# streams_v05.net
KiCad netlist of a schematic drawn in EAGLE
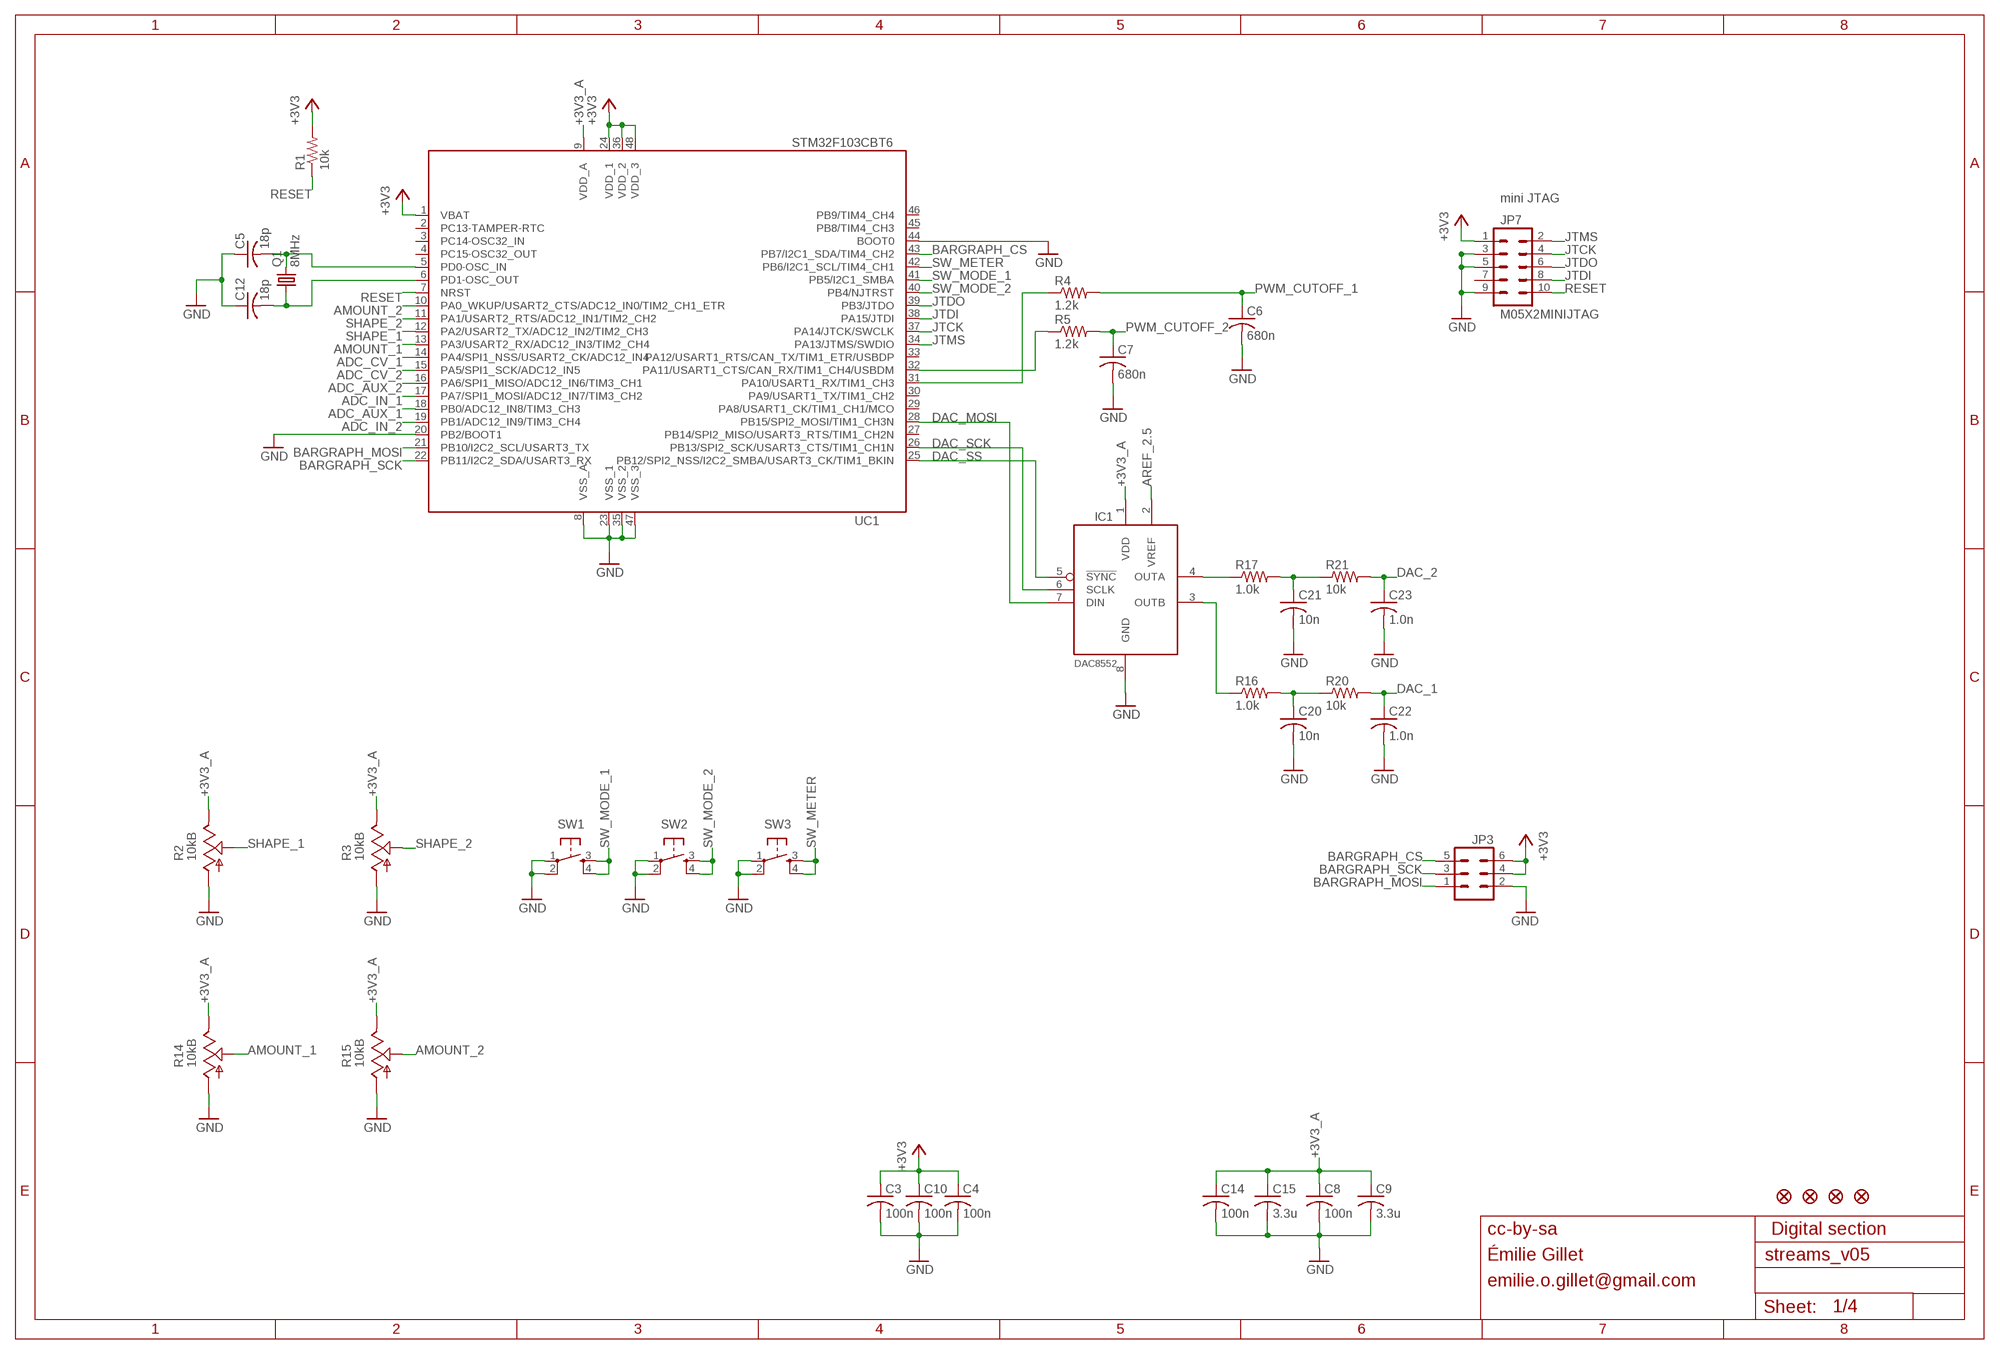
[diagram p0: schematic, sheet 1]
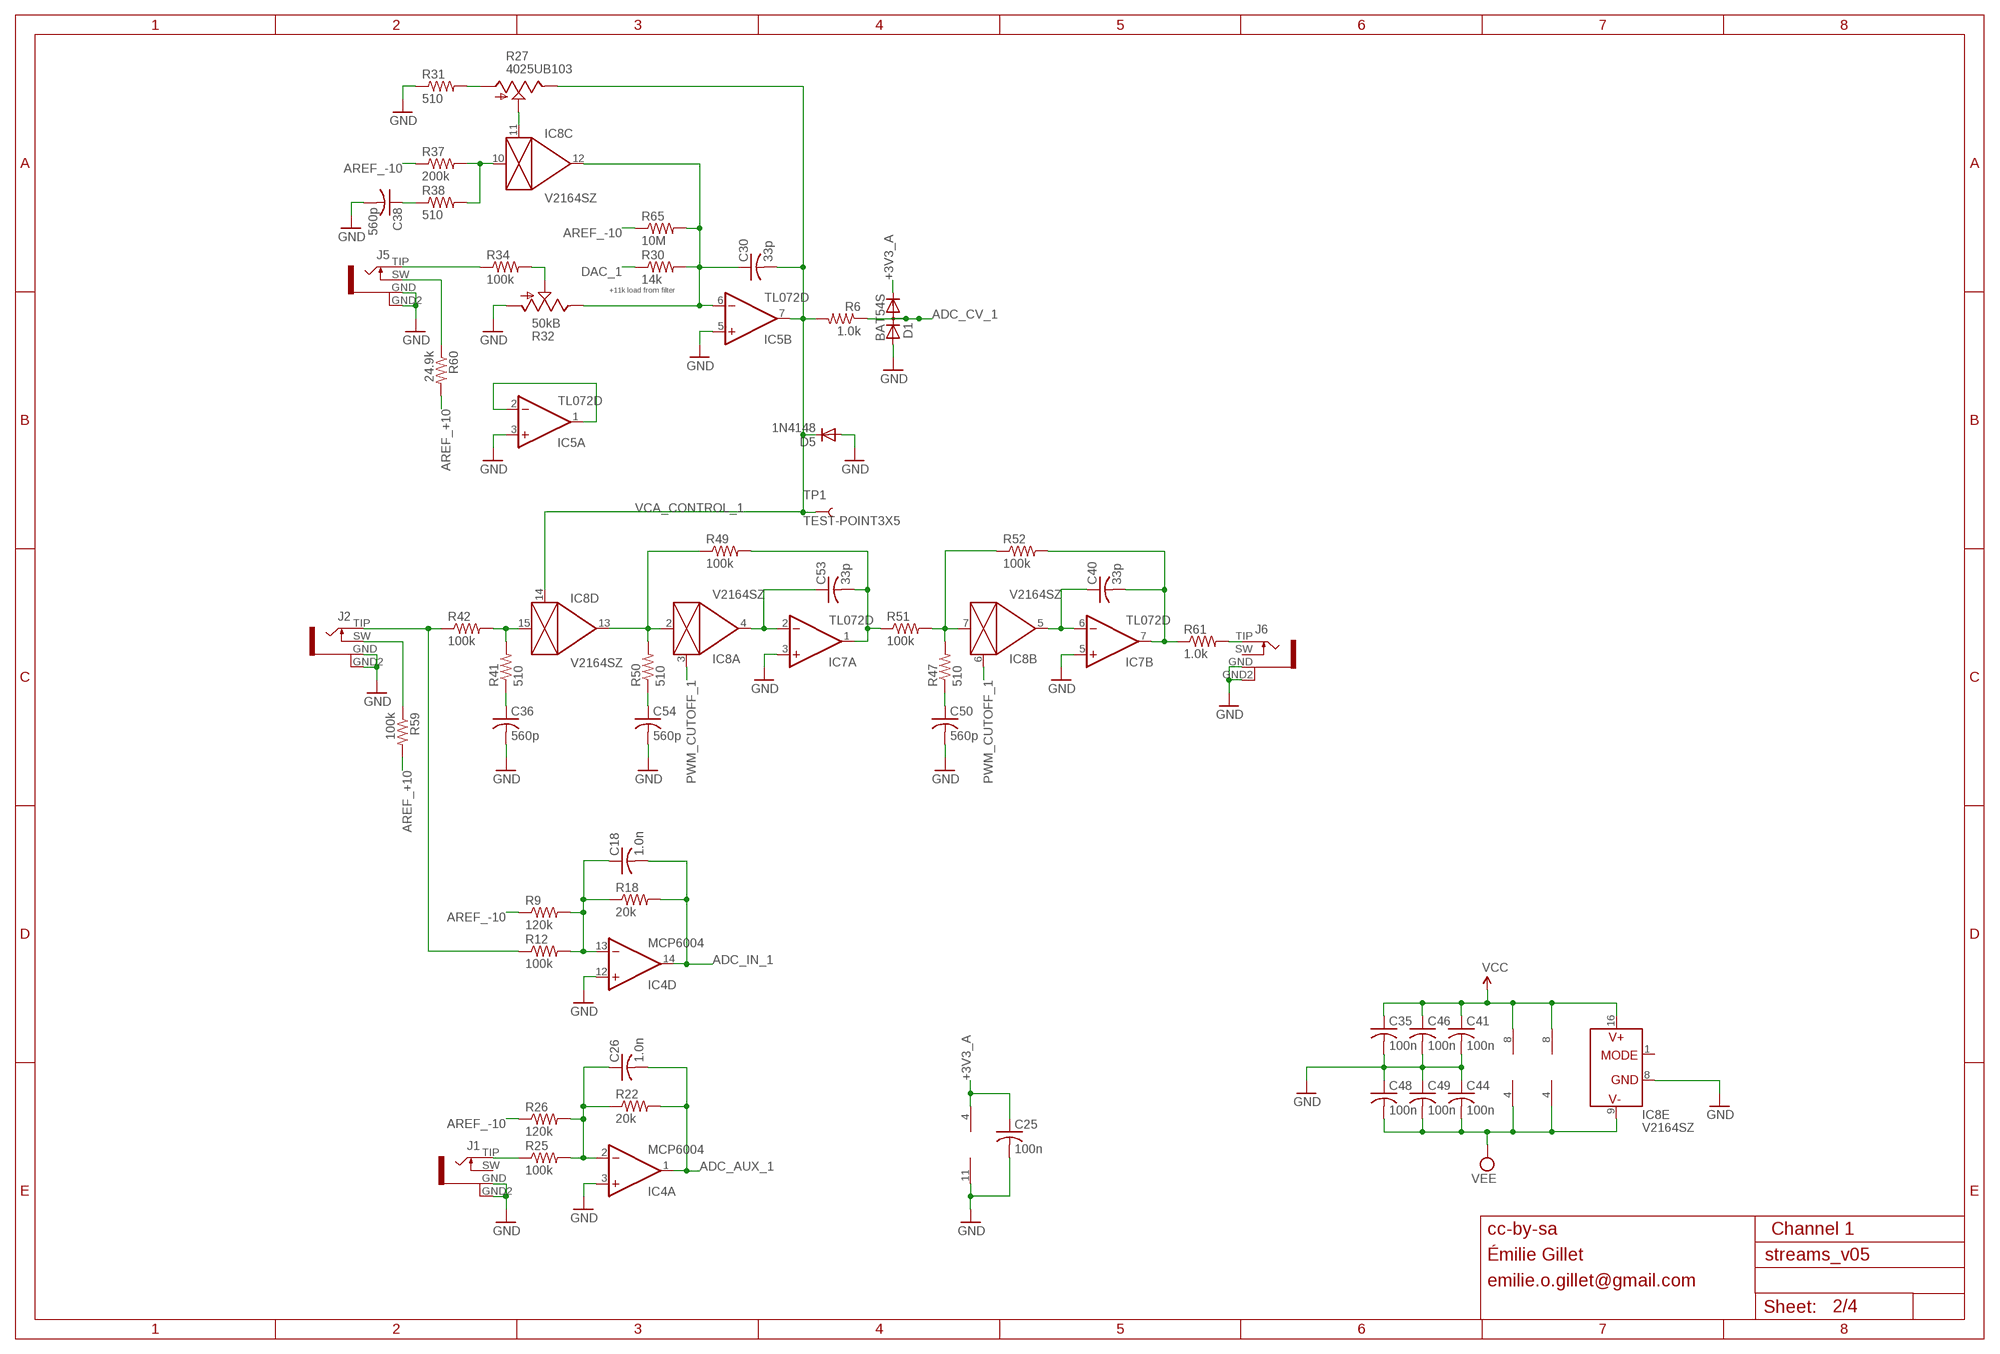
[diagram p1: schematic, sheet 2]
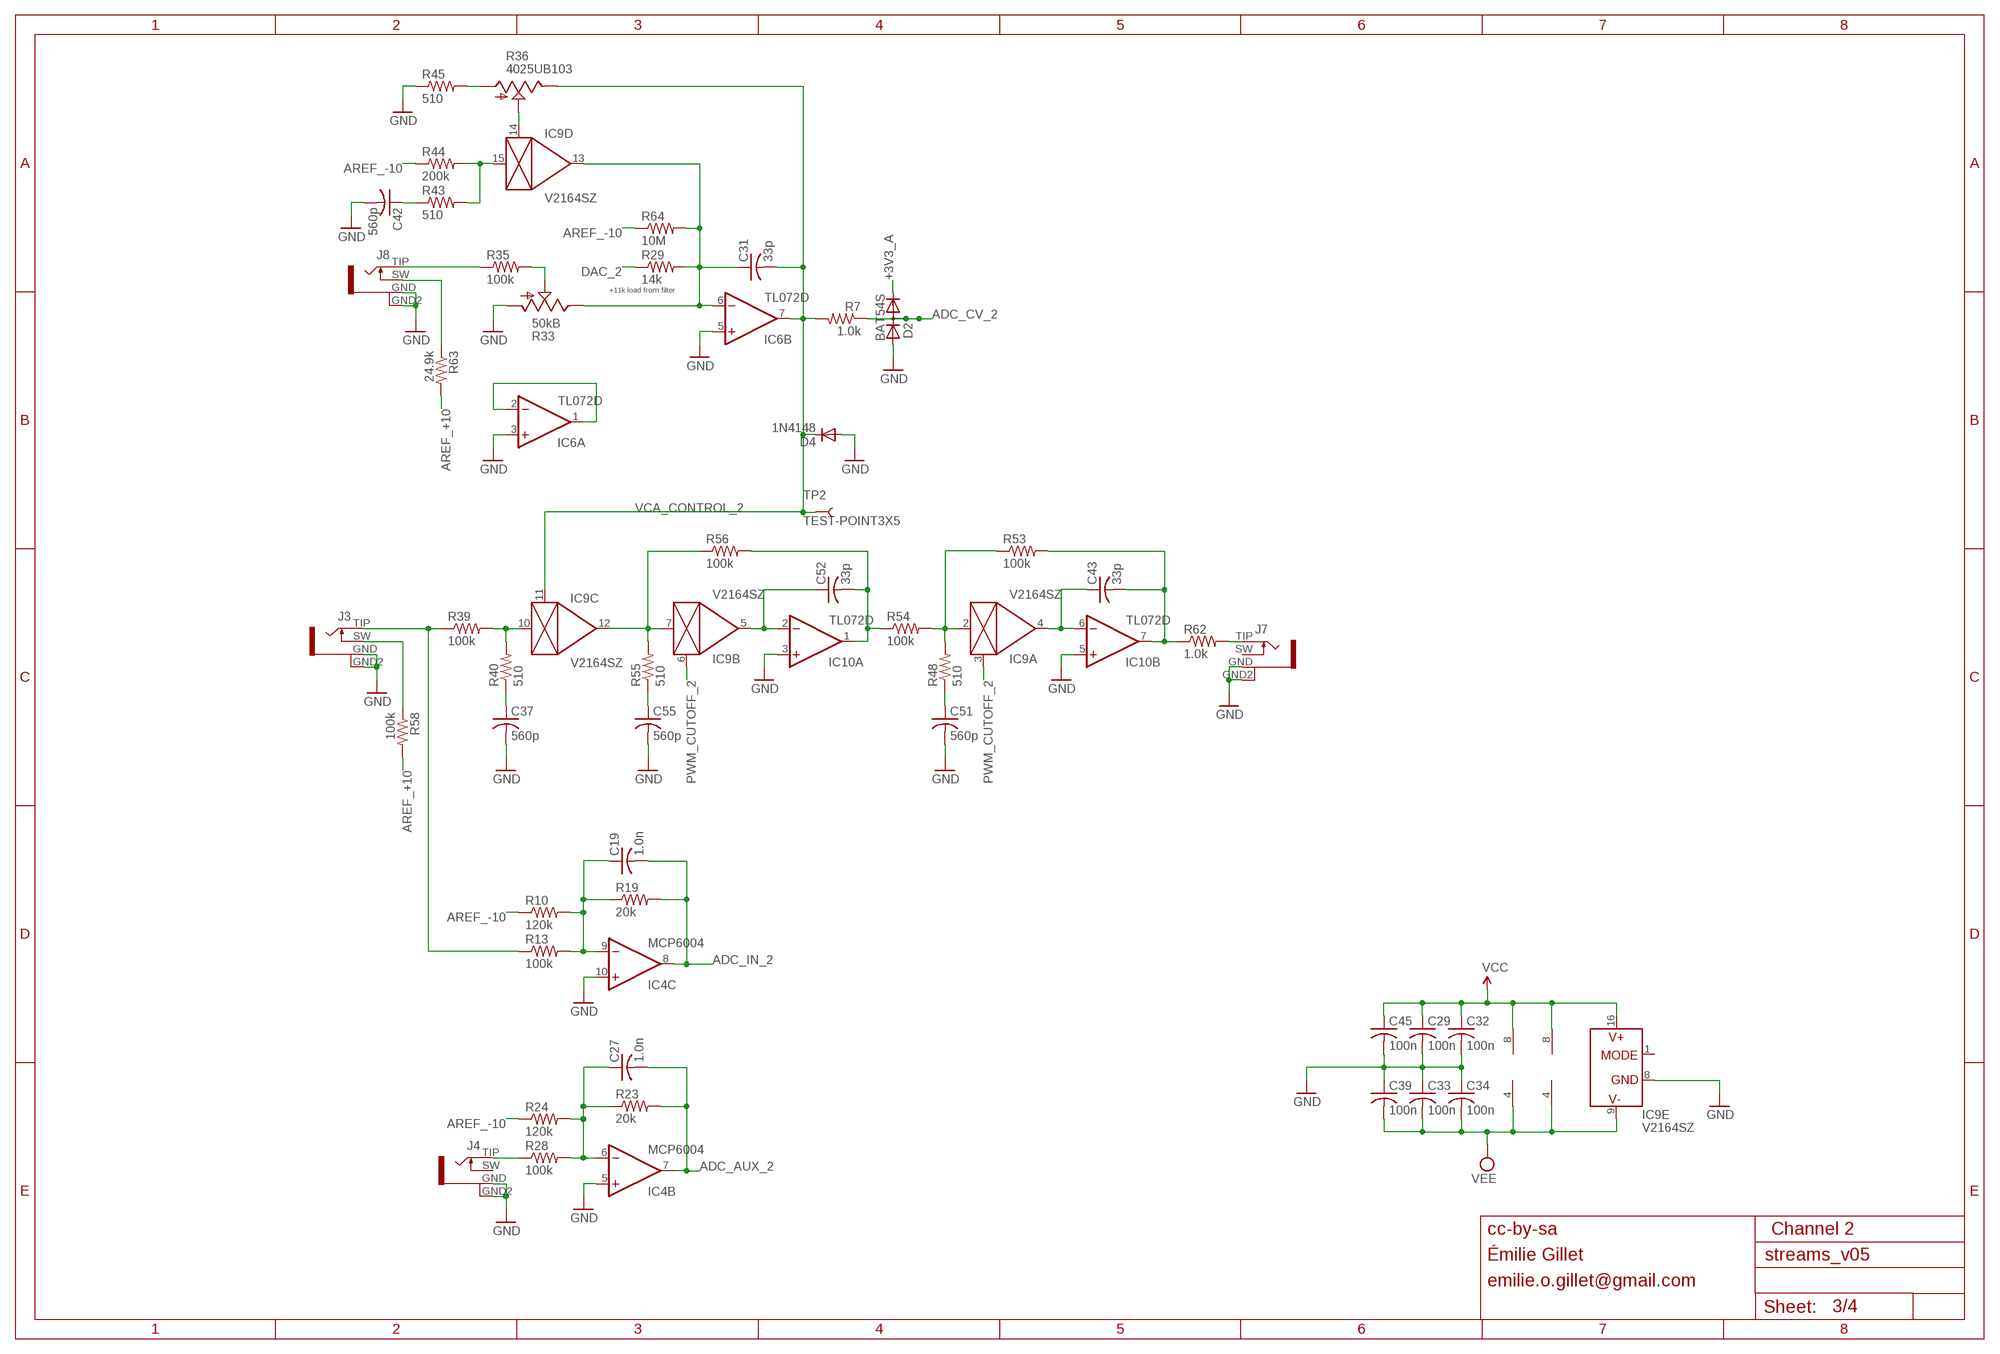
[diagram p2: schematic, sheet 3]
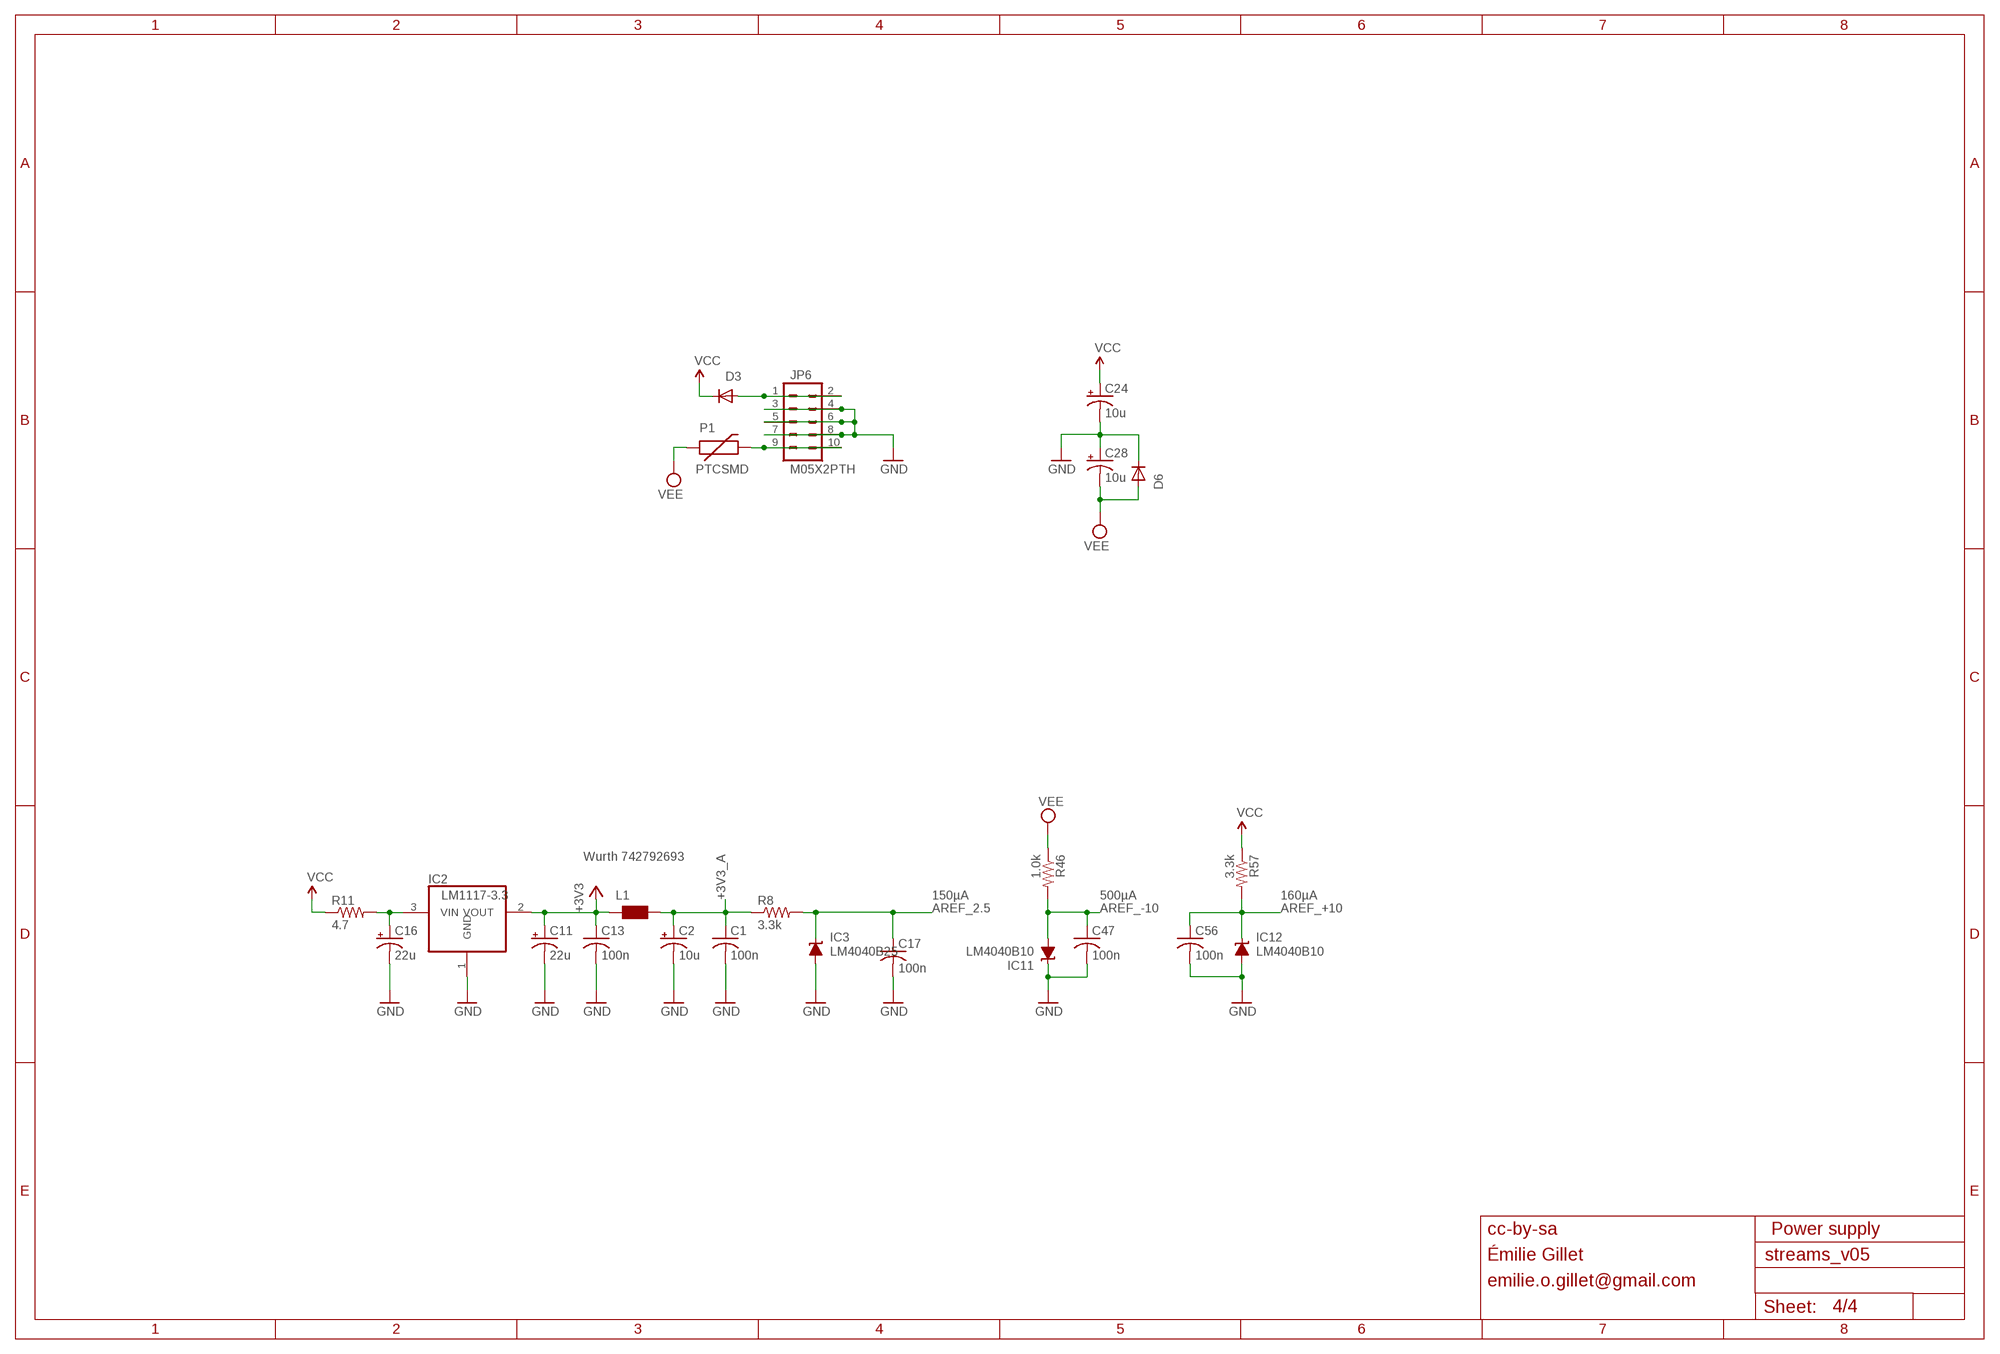
[diagram p3: schematic, sheet 4]

(export (version "E")
  (design (tool "Eeschema 10.0.6"))
  (components
    (comp (ref "C19")
      (value "1.0n")
      (footprint "eagle-import:C0603")
      (libsource (lib "eagle-import") (part "C-USC0603"))
    )
    (comp (ref "C27")
      (value "1.0n")
      (footprint "eagle-import:C0603")
      (libsource (lib "eagle-import") (part "C-USC0603"))
    )
    (comp (ref "C29")
      (value "100n")
      (footprint "eagle-import:C0603")
      (libsource (lib "eagle-import") (part "C-USC0603"))
    )
    (comp (ref "C31")
      (value "33p")
      (footprint "eagle-import:C0603")
      (libsource (lib "eagle-import") (part "C-USC0603"))
    )
    (comp (ref "C32")
      (value "100n")
      (footprint "eagle-import:C0603")
      (libsource (lib "eagle-import") (part "C-USC0603"))
    )
    (comp (ref "C33")
      (value "100n")
      (footprint "eagle-import:C0603")
      (libsource (lib "eagle-import") (part "C-USC0603"))
    )
    (comp (ref "C34")
      (value "100n")
      (footprint "eagle-import:C0603")
      (libsource (lib "eagle-import") (part "C-USC0603"))
    )
    (comp (ref "C37")
      (value "560p")
      (footprint "eagle-import:C0603")
      (libsource (lib "eagle-import") (part "C-USC0603"))
    )
    (comp (ref "C39")
      (value "100n")
      (footprint "eagle-import:C0603")
      (libsource (lib "eagle-import") (part "C-USC0603"))
    )
    (comp (ref "C42")
      (value "560p")
      (footprint "eagle-import:C0603")
      (libsource (lib "eagle-import") (part "C-USC0603"))
    )
    (comp (ref "C43")
      (value "33p")
      (footprint "eagle-import:C0603")
      (libsource (lib "eagle-import") (part "C-USC0603"))
    )
    (comp (ref "C45")
      (value "100n")
      (footprint "eagle-import:C0603")
      (libsource (lib "eagle-import") (part "C-USC0603"))
    )
    (comp (ref "C51")
      (value "560p")
      (footprint "eagle-import:C0603")
      (libsource (lib "eagle-import") (part "C-USC0603"))
    )
    (comp (ref "C52")
      (value "33p")
      (footprint "eagle-import:C0603")
      (libsource (lib "eagle-import") (part "C-USC0603"))
    )
    (comp (ref "C55")
      (value "560p")
      (footprint "eagle-import:C0603")
      (libsource (lib "eagle-import") (part "C-USC0603"))
    )
    (comp (ref "D2")
      (value "BAT54S")
      (footprint "eagle-import:SOT23")
      (libsource (lib "eagle-import") (part "DIODE_2CACA-SOT23"))
    )
    (comp (ref "D4")
      (value "1N4148")
      (footprint "eagle-import:SOD323-W")
      (libsource (lib "eagle-import") (part "DIODE-SOD323-W"))
    )
    (comp (ref "IC4")
      (value "MCP6004")
      (footprint "eagle-import:SO14")
      (libsource (lib "eagle-import") (part "TL074D"))
    )
    (comp (ref "IC6")
      (value "TL072D")
      (footprint "eagle-import:SO08")
      (libsource (lib "eagle-import") (part "TL072D"))
    )
    (comp (ref "IC9")
      (value "V2164SZ")
      (footprint "eagle-import:SOIC16N")
      (libsource (lib "eagle-import") (part "SSM2164S"))
    )
    (comp (ref "IC10")
      (value "TL072D")
      (footprint "eagle-import:SO08")
      (libsource (lib "eagle-import") (part "TL072D"))
    )
    (comp (ref "J3")
      (value "PJ301WQP")
      (footprint "eagle-import:WQP_PJ_301BM_WIDER")
      (libsource (lib "eagle-import") (part "PJ301WQP"))
    )
    (comp (ref "J4")
      (value "PJ301WQP")
      (footprint "eagle-import:WQP_PJ_301BM_WIDER")
      (libsource (lib "eagle-import") (part "PJ301WQP"))
    )
    (comp (ref "J7")
      (value "PJ301WQP")
      (footprint "eagle-import:WQP_PJ_301BM_WIDER")
      (libsource (lib "eagle-import") (part "PJ301WQP"))
    )
    (comp (ref "J8")
      (value "PJ301WQP")
      (footprint "eagle-import:WQP_PJ_301BM_WIDER")
      (libsource (lib "eagle-import") (part "PJ301WQP"))
    )
    (comp (ref "R7")
      (value "1.0k")
      (footprint "eagle-import:R0603")
      (libsource (lib "eagle-import") (part "R-US_R0603"))
    )
    (comp (ref "R10")
      (value "120k")
      (footprint "eagle-import:R0603")
      (libsource (lib "eagle-import") (part "R-US_R0603"))
    )
    (comp (ref "R13")
      (value "100k")
      (footprint "eagle-import:R0603")
      (libsource (lib "eagle-import") (part "R-US_R0603"))
    )
    (comp (ref "R19")
      (value "20k")
      (footprint "eagle-import:R0603")
      (libsource (lib "eagle-import") (part "R-US_R0603"))
    )
    (comp (ref "R23")
      (value "20k")
      (footprint "eagle-import:R0603")
      (libsource (lib "eagle-import") (part "R-US_R0603"))
    )
    (comp (ref "R24")
      (value "120k")
      (footprint "eagle-import:R0603")
      (libsource (lib "eagle-import") (part "R-US_R0603"))
    )
    (comp (ref "R28")
      (value "100k")
      (footprint "eagle-import:R0603")
      (libsource (lib "eagle-import") (part "R-US_R0603"))
    )
    (comp (ref "R29")
      (value "14k")
      (footprint "eagle-import:R0603")
      (libsource (lib "eagle-import") (part "R-US_R0603"))
    )
    (comp (ref "R33")
      (value "50kB")
      (footprint "eagle-import:ALPS_POT_VERTICAL_PS")
      (libsource (lib "eagle-import") (part "POT_USVERTICAL_PS"))
    )
    (comp (ref "R35")
      (value "100k")
      (footprint "eagle-import:R0603")
      (libsource (lib "eagle-import") (part "R-US_R0603"))
    )
    (comp (ref "R36")
      (value "4025UB103")
      (footprint "eagle-import:ALPS_POT_VERTICAL")
      (libsource (lib "eagle-import") (part "POT_USVERTICAL"))
    )
    (comp (ref "R39")
      (value "100k")
      (footprint "eagle-import:R0603")
      (libsource (lib "eagle-import") (part "R-US_R0603"))
    )
    (comp (ref "R40")
      (value "510")
      (footprint "eagle-import:R0603")
      (libsource (lib "eagle-import") (part "R-US_R0603"))
    )
    (comp (ref "R43")
      (value "510")
      (footprint "eagle-import:R0603")
      (libsource (lib "eagle-import") (part "R-US_R0603"))
    )
    (comp (ref "R44")
      (value "200k")
      (footprint "eagle-import:R0603")
      (libsource (lib "eagle-import") (part "R-US_R0603"))
    )
    (comp (ref "R45")
      (value "510")
      (footprint "eagle-import:R0603")
      (libsource (lib "eagle-import") (part "R-US_R0603"))
    )
    (comp (ref "R48")
      (value "510")
      (footprint "eagle-import:R0603")
      (libsource (lib "eagle-import") (part "R-US_R0603"))
    )
    (comp (ref "R53")
      (value "100k")
      (footprint "eagle-import:R0603")
      (libsource (lib "eagle-import") (part "R-US_R0603"))
    )
    (comp (ref "R54")
      (value "100k")
      (footprint "eagle-import:R0603")
      (libsource (lib "eagle-import") (part "R-US_R0603"))
    )
    (comp (ref "R55")
      (value "510")
      (footprint "eagle-import:R0603")
      (libsource (lib "eagle-import") (part "R-US_R0603"))
    )
    (comp (ref "R56")
      (value "100k")
      (footprint "eagle-import:R0603")
      (libsource (lib "eagle-import") (part "R-US_R0603"))
    )
    (comp (ref "R58")
      (value "100k")
      (footprint "eagle-import:R0603")
      (libsource (lib "eagle-import") (part "R-US_R0603"))
    )
    (comp (ref "R62")
      (value "1.0k")
      (footprint "eagle-import:R0603")
      (libsource (lib "eagle-import") (part "R-US_R0603"))
    )
    (comp (ref "R63")
      (value "24.9k")
      (footprint "eagle-import:R0603")
      (libsource (lib "eagle-import") (part "R-US_R0603"))
    )
    (comp (ref "R64")
      (value "10M")
      (footprint "eagle-import:R0603")
      (libsource (lib "eagle-import") (part "R-US_R0603"))
    )
    (comp (ref "TP2")
      (value "TEST-POINT3X5")
      (footprint "eagle-import:PAD.03X.05")
      (libsource (lib "eagle-import") (part "TEST-POINT3X5"))
    )
    (comp (ref "C3")
      (value "100n")
      (footprint "eagle-import:C0603")
      (libsource (lib "eagle-import") (part "C-USC0603"))
    )
    (comp (ref "C4")
      (value "100n")
      (footprint "eagle-import:C0603")
      (libsource (lib "eagle-import") (part "C-USC0603"))
    )
    (comp (ref "C5")
      (value "18p")
      (footprint "eagle-import:C0603")
      (libsource (lib "eagle-import") (part "C-USC0603"))
    )
    (comp (ref "C6")
      (value "680n")
      (footprint "eagle-import:C0603")
      (libsource (lib "eagle-import") (part "C-USC0603"))
    )
    (comp (ref "C7")
      (value "680n")
      (footprint "eagle-import:C0603")
      (libsource (lib "eagle-import") (part "C-USC0603"))
    )
    (comp (ref "C8")
      (value "100n")
      (footprint "eagle-import:C0603")
      (libsource (lib "eagle-import") (part "C-USC0603"))
    )
    (comp (ref "C9")
      (value "3.3u")
      (footprint "eagle-import:C0603")
      (libsource (lib "eagle-import") (part "C-USC0603"))
    )
    (comp (ref "C10")
      (value "100n")
      (footprint "eagle-import:C0603")
      (libsource (lib "eagle-import") (part "C-USC0603"))
    )
    (comp (ref "C12")
      (value "18p")
      (footprint "eagle-import:C0603")
      (libsource (lib "eagle-import") (part "C-USC0603"))
    )
    (comp (ref "C14")
      (value "100n")
      (footprint "eagle-import:C0603")
      (libsource (lib "eagle-import") (part "C-USC0603"))
    )
    (comp (ref "C15")
      (value "3.3u")
      (footprint "eagle-import:C0603")
      (libsource (lib "eagle-import") (part "C-USC0603"))
    )
    (comp (ref "C20")
      (value "10n")
      (footprint "eagle-import:C0603")
      (libsource (lib "eagle-import") (part "C-USC0603"))
    )
    (comp (ref "C21")
      (value "10n")
      (footprint "eagle-import:C0603")
      (libsource (lib "eagle-import") (part "C-USC0603"))
    )
    (comp (ref "C22")
      (value "1.0n")
      (footprint "eagle-import:C0603")
      (libsource (lib "eagle-import") (part "C-USC0603"))
    )
    (comp (ref "C23")
      (value "1.0n")
      (footprint "eagle-import:C0603")
      (libsource (lib "eagle-import") (part "C-USC0603"))
    )
    (comp (ref "IC1")
      (value "DAC8552")
      (footprint "eagle-import:MSOP-8")
      (libsource (lib "eagle-import") (part "DAC8552"))
    )
    (comp (ref "JP1")
      (value "FIDUCIAL1X2")
      (footprint "eagle-import:FIDUCIAL-1X2")
      (libsource (lib "eagle-import") (part "FIDUCIAL1X2"))
    )
    (comp (ref "JP2")
      (value "FIDUCIAL1X2")
      (footprint "eagle-import:FIDUCIAL-1X2")
      (libsource (lib "eagle-import") (part "FIDUCIAL1X2"))
    )
    (comp (ref "JP3")
      (value "M03X2BOTTOM")
      (footprint "eagle-import:2X3_BOTTOM")
      (libsource (lib "eagle-import") (part "M03X2BOTTOM"))
    )
    (comp (ref "JP4")
      (value "FIDUCIAL1X2")
      (footprint "eagle-import:FIDUCIAL-1X2")
      (libsource (lib "eagle-import") (part "FIDUCIAL1X2"))
    )
    (comp (ref "JP5")
      (value "FIDUCIAL1X2")
      (footprint "eagle-import:FIDUCIAL-1X2")
      (libsource (lib "eagle-import") (part "FIDUCIAL1X2"))
    )
    (comp (ref "JP7")
      (value "M05X2MINIJTAG")
      (footprint "eagle-import:2X5-1.27")
      (libsource (lib "eagle-import") (part "M05X2MINIJTAG"))
    )
    (comp (ref "Q1")
      (value "8MHz")
      (footprint "eagle-import:HC49UP")
      (libsource (lib "eagle-import") (part "CRYSTALHC49UP"))
    )
    (comp (ref "R1")
      (value "10k")
      (footprint "eagle-import:R0603")
      (libsource (lib "eagle-import") (part "R-US_R0603"))
    )
    (comp (ref "R2")
      (value "10kB")
      (footprint "eagle-import:ALPS_POT_VERTICAL_PS")
      (libsource (lib "eagle-import") (part "POT_USVERTICAL_PS"))
    )
    (comp (ref "R3")
      (value "10kB")
      (footprint "eagle-import:ALPS_POT_VERTICAL_PS")
      (libsource (lib "eagle-import") (part "POT_USVERTICAL_PS"))
    )
    (comp (ref "R4")
      (value "1.2k")
      (footprint "eagle-import:R0603")
      (libsource (lib "eagle-import") (part "R-US_R0603"))
    )
    (comp (ref "R5")
      (value "1.2k")
      (footprint "eagle-import:R0603")
      (libsource (lib "eagle-import") (part "R-US_R0603"))
    )
    (comp (ref "R14")
      (value "10kB")
      (footprint "eagle-import:ALPS_POT_VERTICAL_PS")
      (libsource (lib "eagle-import") (part "POT_USVERTICAL_PS"))
    )
    (comp (ref "R15")
      (value "10kB")
      (footprint "eagle-import:ALPS_POT_VERTICAL_PS")
      (libsource (lib "eagle-import") (part "POT_USVERTICAL_PS"))
    )
    (comp (ref "R16")
      (value "1.0k")
      (footprint "eagle-import:R0603")
      (libsource (lib "eagle-import") (part "R-US_R0603"))
    )
    (comp (ref "R17")
      (value "1.0k")
      (footprint "eagle-import:R0603")
      (libsource (lib "eagle-import") (part "R-US_R0603"))
    )
    (comp (ref "R20")
      (value "10k")
      (footprint "eagle-import:R0603")
      (libsource (lib "eagle-import") (part "R-US_R0603"))
    )
    (comp (ref "R21")
      (value "10k")
      (footprint "eagle-import:R0603")
      (libsource (lib "eagle-import") (part "R-US_R0603"))
    )
    (comp (ref "SW1")
      (value "TAC_SWITCHPTH")
      (footprint "eagle-import:TACTILE-PTH")
      (libsource (lib "eagle-import") (part "TAC_SWITCHPTH"))
    )
    (comp (ref "SW2")
      (value "TAC_SWITCHPTH")
      (footprint "eagle-import:TACTILE-PTH")
      (libsource (lib "eagle-import") (part "TAC_SWITCHPTH"))
    )
    (comp (ref "SW3")
      (value "TAC_SWITCHPTH")
      (footprint "eagle-import:TACTILE-PTH")
      (libsource (lib "eagle-import") (part "TAC_SWITCHPTH"))
    )
    (comp (ref "UC1")
      (value "STM32F103CBT6")
      (footprint "eagle-import:LQFP48")
      (libsource (lib "eagle-import") (part "STM32F103CB"))
    )
    (comp (ref "C1")
      (value "100n")
      (footprint "eagle-import:C0603")
      (libsource (lib "eagle-import") (part "C-USC0603"))
    )
    (comp (ref "C2")
      (value "10u")
      (footprint "eagle-import:PANASONIC_B")
      (libsource (lib "eagle-import") (part "CPOL-USB"))
    )
    (comp (ref "C11")
      (value "22u")
      (footprint "eagle-import:PANASONIC_B")
      (libsource (lib "eagle-import") (part "CPOL-USB"))
    )
    (comp (ref "C13")
      (value "100n")
      (footprint "eagle-import:C0603")
      (libsource (lib "eagle-import") (part "C-USC0603"))
    )
    (comp (ref "C16")
      (value "22u")
      (footprint "eagle-import:PANASONIC_C")
      (libsource (lib "eagle-import") (part "CPOL-USC"))
    )
    (comp (ref "C17")
      (value "100n")
      (footprint "eagle-import:C0603")
      (libsource (lib "eagle-import") (part "C-USC0603"))
    )
    (comp (ref "C24")
      (value "10u")
      (footprint "eagle-import:PANASONIC_B")
      (libsource (lib "eagle-import") (part "CPOL-USB"))
    )
    (comp (ref "C28")
      (value "10u")
      (footprint "eagle-import:PANASONIC_B")
      (libsource (lib "eagle-import") (part "CPOL-USB"))
    )
    (comp (ref "C47")
      (value "100n")
      (footprint "eagle-import:C0603")
      (libsource (lib "eagle-import") (part "C-USC0603"))
    )
    (comp (ref "C56")
      (value "100n")
      (footprint "eagle-import:C0603")
      (libsource (lib "eagle-import") (part "C-USC0603"))
    )
    (comp (ref "D3")
      (value "1N5819HW")
      (footprint "eagle-import:SOD123")
      (libsource (lib "eagle-import") (part "DIODE-SOD123"))
    )
    (comp (ref "D6")
      (value "1N5819HW")
      (footprint "eagle-import:SOD123")
      (libsource (lib "eagle-import") (part "DIODE-SOD123"))
    )
    (comp (ref "IC2")
      (value "LM1117-3.3")
      (footprint "eagle-import:SOT223")
      (libsource (lib "eagle-import") (part "REG1117"))
    )
    (comp (ref "IC3")
      (value "LM4040B25")
      (footprint "eagle-import:DBZ_R-PDSO-G3")
      (libsource (lib "eagle-import") (part "LM4041DBZB12"))
    )
    (comp (ref "IC11")
      (value "LM4040B10")
      (footprint "eagle-import:DBZ_R-PDSO-G3")
      (libsource (lib "eagle-import") (part "LM4041DBZB12"))
    )
    (comp (ref "IC12")
      (value "LM4040B10")
      (footprint "eagle-import:DBZ_R-PDSO-G3")
      (libsource (lib "eagle-import") (part "LM4041DBZB12"))
    )
    (comp (ref "JP6")
      (value "M05X2PTH")
      (footprint "eagle-import:AVR_ICSP")
      (libsource (lib "eagle-import") (part "M05X2PTH"))
    )
    (comp (ref "L1")
      (value "WE-CBF_0603")
      (footprint "eagle-import:0603")
      (libsource (lib "eagle-import") (part "WE-CBF_0603"))
    )
    (comp (ref "P1")
      (value "PTCSMD")
      (footprint "eagle-import:PTC-1206")
      (libsource (lib "eagle-import") (part "PTCSMD"))
    )
    (comp (ref "R8")
      (value "3.3k")
      (footprint "eagle-import:R0603")
      (libsource (lib "eagle-import") (part "R-US_R0603"))
    )
    (comp (ref "R11")
      (value "4.7")
      (footprint "eagle-import:R1206")
      (libsource (lib "eagle-import") (part "R-US_R1206"))
    )
    (comp (ref "R46")
      (value "1.0k")
      (footprint "eagle-import:R0603")
      (libsource (lib "eagle-import") (part "R-US_R0603"))
    )
    (comp (ref "R57")
      (value "3.3k")
      (footprint "eagle-import:R0603")
      (libsource (lib "eagle-import") (part "R-US_R0603"))
    )
    (comp (ref "C18")
      (value "1.0n")
      (footprint "eagle-import:C0603")
      (libsource (lib "eagle-import") (part "C-USC0603"))
    )
    (comp (ref "C25")
      (value "100n")
      (footprint "eagle-import:C0603")
      (libsource (lib "eagle-import") (part "C-USC0603"))
    )
    (comp (ref "C26")
      (value "1.0n")
      (footprint "eagle-import:C0603")
      (libsource (lib "eagle-import") (part "C-USC0603"))
    )
    (comp (ref "C30")
      (value "33p")
      (footprint "eagle-import:C0603")
      (libsource (lib "eagle-import") (part "C-USC0603"))
    )
    (comp (ref "C35")
      (value "100n")
      (footprint "eagle-import:C0603")
      (libsource (lib "eagle-import") (part "C-USC0603"))
    )
    (comp (ref "C36")
      (value "560p")
      (footprint "eagle-import:C0603")
      (libsource (lib "eagle-import") (part "C-USC0603"))
    )
    (comp (ref "C38")
      (value "560p")
      (footprint "eagle-import:C0603")
      (libsource (lib "eagle-import") (part "C-USC0603"))
    )
    (comp (ref "C40")
      (value "33p")
      (footprint "eagle-import:C0603")
      (libsource (lib "eagle-import") (part "C-USC0603"))
    )
    (comp (ref "C41")
      (value "100n")
      (footprint "eagle-import:C0603")
      (libsource (lib "eagle-import") (part "C-USC0603"))
    )
    (comp (ref "C44")
      (value "100n")
      (footprint "eagle-import:C0603")
      (libsource (lib "eagle-import") (part "C-USC0603"))
    )
    (comp (ref "C46")
      (value "100n")
      (footprint "eagle-import:C0603")
      (libsource (lib "eagle-import") (part "C-USC0603"))
    )
    (comp (ref "C48")
      (value "100n")
      (footprint "eagle-import:C0603")
      (libsource (lib "eagle-import") (part "C-USC0603"))
    )
    (comp (ref "C49")
      (value "100n")
      (footprint "eagle-import:C0603")
      (libsource (lib "eagle-import") (part "C-USC0603"))
    )
    (comp (ref "C50")
      (value "560p")
      (footprint "eagle-import:C0603")
      (libsource (lib "eagle-import") (part "C-USC0603"))
    )
    (comp (ref "C53")
      (value "33p")
      (footprint "eagle-import:C0603")
      (libsource (lib "eagle-import") (part "C-USC0603"))
    )
    (comp (ref "C54")
      (value "560p")
      (footprint "eagle-import:C0603")
      (libsource (lib "eagle-import") (part "C-USC0603"))
    )
    (comp (ref "D1")
      (value "BAT54S")
      (footprint "eagle-import:SOT23")
      (libsource (lib "eagle-import") (part "DIODE_2CACA-SOT23"))
    )
    (comp (ref "D5")
      (value "1N4148")
      (footprint "eagle-import:SOD323-W")
      (libsource (lib "eagle-import") (part "DIODE-SOD323-W"))
    )
    (comp (ref "IC5")
      (value "TL072D")
      (footprint "eagle-import:SO08")
      (libsource (lib "eagle-import") (part "TL072D"))
    )
    (comp (ref "IC7")
      (value "TL072D")
      (footprint "eagle-import:SO08")
      (libsource (lib "eagle-import") (part "TL072D"))
    )
    (comp (ref "IC8")
      (value "V2164SZ")
      (footprint "eagle-import:SOIC16N")
      (libsource (lib "eagle-import") (part "SSM2164S"))
    )
    (comp (ref "J1")
      (value "PJ301WQP")
      (footprint "eagle-import:WQP_PJ_301BM_WIDER")
      (libsource (lib "eagle-import") (part "PJ301WQP"))
    )
    (comp (ref "J2")
      (value "PJ301WQP")
      (footprint "eagle-import:WQP_PJ_301BM_WIDER")
      (libsource (lib "eagle-import") (part "PJ301WQP"))
    )
    (comp (ref "J5")
      (value "PJ301WQP")
      (footprint "eagle-import:WQP_PJ_301BM_WIDER")
      (libsource (lib "eagle-import") (part "PJ301WQP"))
    )
    (comp (ref "J6")
      (value "PJ301WQP")
      (footprint "eagle-import:WQP_PJ_301BM_WIDER")
      (libsource (lib "eagle-import") (part "PJ301WQP"))
    )
    (comp (ref "R6")
      (value "1.0k")
      (footprint "eagle-import:R0603")
      (libsource (lib "eagle-import") (part "R-US_R0603"))
    )
    (comp (ref "R9")
      (value "120k")
      (footprint "eagle-import:R0603")
      (libsource (lib "eagle-import") (part "R-US_R0603"))
    )
    (comp (ref "R12")
      (value "100k")
      (footprint "eagle-import:R0603")
      (libsource (lib "eagle-import") (part "R-US_R0603"))
    )
    (comp (ref "R18")
      (value "20k")
      (footprint "eagle-import:R0603")
      (libsource (lib "eagle-import") (part "R-US_R0603"))
    )
    (comp (ref "R22")
      (value "20k")
      (footprint "eagle-import:R0603")
      (libsource (lib "eagle-import") (part "R-US_R0603"))
    )
    (comp (ref "R25")
      (value "100k")
      (footprint "eagle-import:R0603")
      (libsource (lib "eagle-import") (part "R-US_R0603"))
    )
    (comp (ref "R26")
      (value "120k")
      (footprint "eagle-import:R0603")
      (libsource (lib "eagle-import") (part "R-US_R0603"))
    )
    (comp (ref "R27")
      (value "4025UB103")
      (footprint "eagle-import:ALPS_POT_VERTICAL")
      (libsource (lib "eagle-import") (part "POT_USVERTICAL"))
    )
    (comp (ref "R30")
      (value "14k")
      (footprint "eagle-import:R0603")
      (libsource (lib "eagle-import") (part "R-US_R0603"))
    )
    (comp (ref "R31")
      (value "510")
      (footprint "eagle-import:R0603")
      (libsource (lib "eagle-import") (part "R-US_R0603"))
    )
    (comp (ref "R32")
      (value "50kB")
      (footprint "eagle-import:ALPS_POT_VERTICAL_PS")
      (libsource (lib "eagle-import") (part "POT_USVERTICAL_PS"))
    )
    (comp (ref "R34")
      (value "100k")
      (footprint "eagle-import:R0603")
      (libsource (lib "eagle-import") (part "R-US_R0603"))
    )
    (comp (ref "R37")
      (value "200k")
      (footprint "eagle-import:R0603")
      (libsource (lib "eagle-import") (part "R-US_R0603"))
    )
    (comp (ref "R38")
      (value "510")
      (footprint "eagle-import:R0603")
      (libsource (lib "eagle-import") (part "R-US_R0603"))
    )
    (comp (ref "R41")
      (value "510")
      (footprint "eagle-import:R0603")
      (libsource (lib "eagle-import") (part "R-US_R0603"))
    )
    (comp (ref "R42")
      (value "100k")
      (footprint "eagle-import:R0603")
      (libsource (lib "eagle-import") (part "R-US_R0603"))
    )
    (comp (ref "R47")
      (value "510")
      (footprint "eagle-import:R0603")
      (libsource (lib "eagle-import") (part "R-US_R0603"))
    )
    (comp (ref "R49")
      (value "100k")
      (footprint "eagle-import:R0603")
      (libsource (lib "eagle-import") (part "R-US_R0603"))
    )
    (comp (ref "R50")
      (value "510")
      (footprint "eagle-import:R0603")
      (libsource (lib "eagle-import") (part "R-US_R0603"))
    )
    (comp (ref "R51")
      (value "100k")
      (footprint "eagle-import:R0603")
      (libsource (lib "eagle-import") (part "R-US_R0603"))
    )
    (comp (ref "R52")
      (value "100k")
      (footprint "eagle-import:R0603")
      (libsource (lib "eagle-import") (part "R-US_R0603"))
    )
    (comp (ref "R59")
      (value "100k")
      (footprint "eagle-import:R0603")
      (libsource (lib "eagle-import") (part "R-US_R0603"))
    )
    (comp (ref "R60")
      (value "24.9k")
      (footprint "eagle-import:R0603")
      (libsource (lib "eagle-import") (part "R-US_R0603"))
    )
    (comp (ref "R61")
      (value "1.0k")
      (footprint "eagle-import:R0603")
      (libsource (lib "eagle-import") (part "R-US_R0603"))
    )
    (comp (ref "R65")
      (value "10M")
      (footprint "eagle-import:R0603")
      (libsource (lib "eagle-import") (part "R-US_R0603"))
    )
    (comp (ref "TP1")
      (value "TEST-POINT3X5")
      (footprint "eagle-import:PAD.03X.05")
      (libsource (lib "eagle-import") (part "TEST-POINT3X5"))
    )
  )
  (nets
    (net (code "1") (name "+3V3") (class "Default")
      (node (ref "C10") (pin "1") (pinfunction "1_1") (pintype "passive"))
      (node (ref "C11") (pin "+") (pinfunction "+_+") (pintype "passive"))
      (node (ref "C13") (pin "1") (pinfunction "1_1") (pintype "passive"))
      (node (ref "C3") (pin "1") (pinfunction "1_1") (pintype "passive"))
      (node (ref "C4") (pin "1") (pinfunction "1_1") (pintype "passive"))
      (node (ref "IC2") (pin "2") (pinfunction "VOUT_2") (pintype "output"))
      (node (ref "JP3") (pin "4") (pinfunction "4_4") (pintype "passive"))
      (node (ref "JP3") (pin "6") (pinfunction "6_6") (pintype "passive"))
      (node (ref "JP7") (pin "1") (pinfunction "1_1") (pintype "passive"))
      (node (ref "L1") (pin "1") (pinfunction "1_1") (pintype "passive"))
      (node (ref "R1") (pin "2") (pinfunction "2_2") (pintype "passive"))
      (node (ref "UC1") (pin "1") (pinfunction "VBAT_1") (pintype "power_in"))
      (node (ref "UC1") (pin "24") (pinfunction "VDD_1_24") (pintype "power_in"))
      (node (ref "UC1") (pin "36") (pinfunction "VDD_2_36") (pintype "power_in"))
      (node (ref "UC1") (pin "48") (pinfunction "VDD_3_48") (pintype "power_in"))
    )
    (net (code "2") (name "+3V3_A") (class "Default")
      (node (ref "C1") (pin "1") (pinfunction "1_1") (pintype "passive"))
      (node (ref "C14") (pin "1") (pinfunction "1_1") (pintype "passive"))
      (node (ref "C15") (pin "1") (pinfunction "1_1") (pintype "passive"))
      (node (ref "C2") (pin "+") (pinfunction "+_+") (pintype "passive"))
      (node (ref "C25") (pin "1") (pinfunction "1_1") (pintype "passive"))
      (node (ref "C8") (pin "1") (pinfunction "1_1") (pintype "passive"))
      (node (ref "C9") (pin "1") (pinfunction "1_1") (pintype "passive"))
      (node (ref "D1") (pin "2") (pinfunction "C_2") (pintype "passive"))
      (node (ref "D2") (pin "2") (pinfunction "C_2") (pintype "passive"))
      (node (ref "IC1") (pin "1") (pinfunction "VDD_1") (pintype "power_in"))
      (node (ref "IC4") (pin "4") (pinfunction "V+_4") (pintype "power_in"))
      (node (ref "L1") (pin "2") (pinfunction "2_2") (pintype "passive"))
      (node (ref "R14") (pin "P$1") (pinfunction "E_P$1") (pintype "passive"))
      (node (ref "R15") (pin "P$1") (pinfunction "E_P$1") (pintype "passive"))
      (node (ref "R2") (pin "P$1") (pinfunction "E_P$1") (pintype "passive"))
      (node (ref "R3") (pin "P$1") (pinfunction "E_P$1") (pintype "passive"))
      (node (ref "R8") (pin "1") (pinfunction "1_1") (pintype "passive"))
      (node (ref "UC1") (pin "9") (pinfunction "VDD_A_9") (pintype "power_in"))
    )
    (net (code "3") (name "ADC_AUX_1") (class "Default")
      (node (ref "C26") (pin "2") (pinfunction "2_2") (pintype "passive"))
      (node (ref "IC4") (pin "1") (pinfunction "OUT_1") (pintype "output"))
      (node (ref "R22") (pin "2") (pinfunction "2_2") (pintype "passive"))
      (node (ref "UC1") (pin "18") (pinfunction "PB0/ADC12_IN8/TIM3_CH3_18") (pintype "bidirectional"))
    )
    (net (code "4") (name "ADC_AUX_2") (class "Default")
      (node (ref "C27") (pin "2") (pinfunction "2_2") (pintype "passive"))
      (node (ref "IC4") (pin "7") (pinfunction "OUT_7") (pintype "output"))
      (node (ref "R23") (pin "2") (pinfunction "2_2") (pintype "passive"))
      (node (ref "UC1") (pin "16") (pinfunction "PA6/SPI1_MISO/ADC12_IN6/TIM3_CH1_16") (pintype "bidirectional"))
    )
    (net (code "5") (name "ADC_CV_1") (class "Default")
      (node (ref "D1") (pin "3") (pinfunction "AC_3") (pintype "passive"))
      (node (ref "R6") (pin "1") (pinfunction "1_1") (pintype "passive"))
      (node (ref "UC1") (pin "14") (pinfunction "PA4/SPI1_NSS/USART2_CK/ADC12_IN4_14") (pintype "bidirectional"))
    )
    (net (code "6") (name "ADC_CV_2") (class "Default")
      (node (ref "D2") (pin "3") (pinfunction "AC_3") (pintype "passive"))
      (node (ref "R7") (pin "1") (pinfunction "1_1") (pintype "passive"))
      (node (ref "UC1") (pin "15") (pinfunction "PA5/SPI1_SCK/ADC12_IN5_15") (pintype "bidirectional"))
    )
    (net (code "7") (name "ADC_IN_1") (class "Default")
      (node (ref "C18") (pin "2") (pinfunction "2_2") (pintype "passive"))
      (node (ref "IC4") (pin "14") (pinfunction "OUT_14") (pintype "output"))
      (node (ref "R18") (pin "2") (pinfunction "2_2") (pintype "passive"))
      (node (ref "UC1") (pin "17") (pinfunction "PA7/SPI1_MOSI/ADC12_IN7/TIM3_CH2_17") (pintype "bidirectional"))
    )
    (net (code "8") (name "ADC_IN_2") (class "Default")
      (node (ref "C19") (pin "2") (pinfunction "2_2") (pintype "passive"))
      (node (ref "IC4") (pin "8") (pinfunction "OUT_8") (pintype "output"))
      (node (ref "R19") (pin "2") (pinfunction "2_2") (pintype "passive"))
      (node (ref "UC1") (pin "19") (pinfunction "PB1/ADC12_IN9/TIM3_CH4_19") (pintype "bidirectional"))
    )
    (net (code "9") (name "AMOUNT_1") (class "Default")
      (node (ref "R14") (pin "P$2") (pinfunction "S_P$2") (pintype "passive"))
      (node (ref "UC1") (pin "13") (pinfunction "PA3/USART2_RX/ADC12_IN3/TIM2_CH4_13") (pintype "bidirectional"))
    )
    (net (code "10") (name "AMOUNT_2") (class "Default")
      (node (ref "R15") (pin "P$2") (pinfunction "S_P$2") (pintype "passive"))
      (node (ref "UC1") (pin "10") (pinfunction "PA0_WKUP/USART2_CTS/ADC12_IN0/TIM2_CH1_ETR_10") (pintype "bidirectional"))
    )
    (net (code "11") (name "AREF_+10") (class "Default")
      (node (ref "C56") (pin "1") (pinfunction "1_1") (pintype "passive"))
      (node (ref "IC12") (pin "1") (pinfunction "C_1") (pintype "passive"))
      (node (ref "R57") (pin "2") (pinfunction "2_2") (pintype "passive"))
      (node (ref "R58") (pin "2") (pinfunction "2_2") (pintype "passive"))
      (node (ref "R59") (pin "2") (pinfunction "2_2") (pintype "passive"))
      (node (ref "R60") (pin "2") (pinfunction "2_2") (pintype "passive"))
      (node (ref "R63") (pin "2") (pinfunction "2_2") (pintype "passive"))
    )
    (net (code "12") (name "AREF_-10") (class "Default")
      (node (ref "C47") (pin "1") (pinfunction "1_1") (pintype "passive"))
      (node (ref "IC11") (pin "2") (pinfunction "A_2") (pintype "passive"))
      (node (ref "R10") (pin "1") (pinfunction "1_1") (pintype "passive"))
      (node (ref "R24") (pin "1") (pinfunction "1_1") (pintype "passive"))
      (node (ref "R26") (pin "1") (pinfunction "1_1") (pintype "passive"))
      (node (ref "R37") (pin "1") (pinfunction "1_1") (pintype "passive"))
      (node (ref "R44") (pin "1") (pinfunction "1_1") (pintype "passive"))
      (node (ref "R46") (pin "2") (pinfunction "2_2") (pintype "passive"))
      (node (ref "R64") (pin "1") (pinfunction "1_1") (pintype "passive"))
      (node (ref "R65") (pin "1") (pinfunction "1_1") (pintype "passive"))
      (node (ref "R9") (pin "1") (pinfunction "1_1") (pintype "passive"))
    )
    (net (code "13") (name "AREF_2.5") (class "Default")
      (node (ref "C17") (pin "1") (pinfunction "1_1") (pintype "passive"))
      (node (ref "IC1") (pin "2") (pinfunction "VREF_2") (pintype "power_in"))
      (node (ref "IC3") (pin "1") (pinfunction "C_1") (pintype "passive"))
      (node (ref "R8") (pin "2") (pinfunction "2_2") (pintype "passive"))
    )
    (net (code "14") (name "BARGRAPH_CS") (class "Default")
      (node (ref "JP3") (pin "5") (pinfunction "5_5") (pintype "passive"))
      (node (ref "UC1") (pin "43") (pinfunction "PB7/I2C1_SDA/TIM4_CH2_43") (pintype "bidirectional"))
    )
    (net (code "15") (name "BARGRAPH_MOSI") (class "Default")
      (node (ref "JP3") (pin "1") (pinfunction "1_1") (pintype "passive"))
      (node (ref "UC1") (pin "21") (pinfunction "PB10/I2C2_SCL/USART3_TX_21") (pintype "input"))
    )
    (net (code "16") (name "BARGRAPH_SCK") (class "Default")
      (node (ref "JP3") (pin "3") (pinfunction "3_3") (pintype "passive"))
      (node (ref "UC1") (pin "22") (pinfunction "PB11/I2C2_SDA/USART3_RX_22") (pintype "input"))
    )
    (net (code "17") (name "DAC_1") (class "Default")
      (node (ref "C22") (pin "1") (pinfunction "1_1") (pintype "passive"))
      (node (ref "R20") (pin "2") (pinfunction "2_2") (pintype "passive"))
      (node (ref "R30") (pin "1") (pinfunction "1_1") (pintype "passive"))
    )
    (net (code "18") (name "DAC_2") (class "Default")
      (node (ref "C23") (pin "1") (pinfunction "1_1") (pintype "passive"))
      (node (ref "R21") (pin "2") (pinfunction "2_2") (pintype "passive"))
      (node (ref "R29") (pin "1") (pinfunction "1_1") (pintype "passive"))
    )
    (net (code "19") (name "DAC_MOSI") (class "Default")
      (node (ref "IC1") (pin "7") (pinfunction "DIN_7") (pintype "bidirectional"))
      (node (ref "UC1") (pin "28") (pinfunction "PB15/SPI2_MOSI/TIM1_CH3N_28") (pintype "input"))
    )
    (net (code "20") (name "DAC_SCK") (class "Default")
      (node (ref "IC1") (pin "6") (pinfunction "SCLK_6") (pintype "bidirectional"))
      (node (ref "UC1") (pin "26") (pinfunction "PB13/SPI2_SCK/USART3_CTS/TIM1_CH1N_26") (pintype "input"))
    )
    (net (code "21") (name "DAC_SS") (class "Default")
      (node (ref "IC1") (pin "5") (pinfunction "~{SYNC}_5") (pintype "bidirectional"))
      (node (ref "UC1") (pin "25") (pinfunction "PB12/SPI2_NSS/I2C2_SMBA/USART3_CK/TIM1_BKIN_25") (pintype "input"))
    )
    (net (code "22") (name "GND") (class "Default")
      (node (ref "C1") (pin "2") (pinfunction "2_2") (pintype "passive"))
      (node (ref "C10") (pin "2") (pinfunction "2_2") (pintype "passive"))
      (node (ref "C11") (pin "-") (pinfunction "-_-") (pintype "passive"))
      (node (ref "C12") (pin "1") (pinfunction "1_1") (pintype "passive"))
      (node (ref "C13") (pin "2") (pinfunction "2_2") (pintype "passive"))
      (node (ref "C14") (pin "2") (pinfunction "2_2") (pintype "passive"))
      (node (ref "C15") (pin "2") (pinfunction "2_2") (pintype "passive"))
      (node (ref "C16") (pin "-") (pinfunction "-_-") (pintype "passive"))
      (node (ref "C17") (pin "2") (pinfunction "2_2") (pintype "passive"))
      (node (ref "C2") (pin "-") (pinfunction "-_-") (pintype "passive"))
      (node (ref "C20") (pin "2") (pinfunction "2_2") (pintype "passive"))
      (node (ref "C21") (pin "2") (pinfunction "2_2") (pintype "passive"))
      (node (ref "C22") (pin "2") (pinfunction "2_2") (pintype "passive"))
      (node (ref "C23") (pin "2") (pinfunction "2_2") (pintype "passive"))
      (node (ref "C24") (pin "-") (pinfunction "-_-") (pintype "passive"))
      (node (ref "C25") (pin "2") (pinfunction "2_2") (pintype "passive"))
      (node (ref "C28") (pin "+") (pinfunction "+_+") (pintype "passive"))
      (node (ref "C29") (pin "2") (pinfunction "2_2") (pintype "passive"))
      (node (ref "C3") (pin "2") (pinfunction "2_2") (pintype "passive"))
      (node (ref "C32") (pin "2") (pinfunction "2_2") (pintype "passive"))
      (node (ref "C33") (pin "1") (pinfunction "1_1") (pintype "passive"))
      (node (ref "C34") (pin "1") (pinfunction "1_1") (pintype "passive"))
      (node (ref "C35") (pin "2") (pinfunction "2_2") (pintype "passive"))
      (node (ref "C36") (pin "2") (pinfunction "2_2") (pintype "passive"))
      (node (ref "C37") (pin "2") (pinfunction "2_2") (pintype "passive"))
      (node (ref "C38") (pin "2") (pinfunction "2_2") (pintype "passive"))
      (node (ref "C39") (pin "1") (pinfunction "1_1") (pintype "passive"))
      (node (ref "C4") (pin "2") (pinfunction "2_2") (pintype "passive"))
      (node (ref "C41") (pin "2") (pinfunction "2_2") (pintype "passive"))
      (node (ref "C42") (pin "2") (pinfunction "2_2") (pintype "passive"))
      (node (ref "C44") (pin "1") (pinfunction "1_1") (pintype "passive"))
      (node (ref "C45") (pin "2") (pinfunction "2_2") (pintype "passive"))
      (node (ref "C46") (pin "2") (pinfunction "2_2") (pintype "passive"))
      (node (ref "C47") (pin "2") (pinfunction "2_2") (pintype "passive"))
      (node (ref "C48") (pin "1") (pinfunction "1_1") (pintype "passive"))
      (node (ref "C49") (pin "1") (pinfunction "1_1") (pintype "passive"))
      (node (ref "C5") (pin "1") (pinfunction "1_1") (pintype "passive"))
      (node (ref "C50") (pin "2") (pinfunction "2_2") (pintype "passive"))
      (node (ref "C51") (pin "2") (pinfunction "2_2") (pintype "passive"))
      (node (ref "C54") (pin "2") (pinfunction "2_2") (pintype "passive"))
      (node (ref "C55") (pin "2") (pinfunction "2_2") (pintype "passive"))
      (node (ref "C56") (pin "2") (pinfunction "2_2") (pintype "passive"))
      (node (ref "C6") (pin "2") (pinfunction "2_2") (pintype "passive"))
      (node (ref "C7") (pin "2") (pinfunction "2_2") (pintype "passive"))
      (node (ref "C8") (pin "2") (pinfunction "2_2") (pintype "passive"))
      (node (ref "C9") (pin "2") (pinfunction "2_2") (pintype "passive"))
      (node (ref "D1") (pin "1") (pinfunction "A_1") (pintype "passive"))
      (node (ref "D2") (pin "1") (pinfunction "A_1") (pintype "passive"))
      (node (ref "D4") (pin "A") (pinfunction "A_A") (pintype "passive"))
      (node (ref "D5") (pin "A") (pinfunction "A_A") (pintype "passive"))
      (node (ref "D6") (pin "C") (pinfunction "C_C") (pintype "passive"))
      (node (ref "IC1") (pin "8") (pinfunction "GND_8") (pintype "power_in"))
      (node (ref "IC10") (pin "3") (pinfunction "+IN_3") (pintype "input"))
      (node (ref "IC10") (pin "5") (pinfunction "+IN_5") (pintype "input"))
      (node (ref "IC11") (pin "1") (pinfunction "C_1") (pintype "passive"))
      (node (ref "IC12") (pin "2") (pinfunction "A_2") (pintype "passive"))
      (node (ref "IC2") (pin "1") (pinfunction "GND_1") (pintype "power_in"))
      (node (ref "IC3") (pin "2") (pinfunction "A_2") (pintype "passive"))
      (node (ref "IC4") (pin "10") (pinfunction "+IN_10") (pintype "input"))
      (node (ref "IC4") (pin "11") (pinfunction "V-_11") (pintype "power_in"))
      (node (ref "IC4") (pin "12") (pinfunction "+IN_12") (pintype "input"))
      (node (ref "IC4") (pin "3") (pinfunction "+IN_3") (pintype "input"))
      (node (ref "IC4") (pin "5") (pinfunction "+IN_5") (pintype "input"))
      (node (ref "IC5") (pin "3") (pinfunction "+IN_3") (pintype "input"))
      (node (ref "IC5") (pin "5") (pinfunction "+IN_5") (pintype "input"))
      (node (ref "IC6") (pin "3") (pinfunction "+IN_3") (pintype "input"))
      (node (ref "IC6") (pin "5") (pinfunction "+IN_5") (pintype "input"))
      (node (ref "IC7") (pin "3") (pinfunction "+IN_3") (pintype "input"))
      (node (ref "IC7") (pin "5") (pinfunction "+IN_5") (pintype "input"))
      (node (ref "IC8") (pin "8") (pinfunction "GND_8") (pintype "power_in"))
      (node (ref "IC9") (pin "8") (pinfunction "GND_8") (pintype "power_in"))
      (node (ref "J1") (pin "GND") (pinfunction "1_GND") (pintype "passive"))
      (node (ref "J1") (pin "GND2") (pinfunction "4_GND2") (pintype "passive"))
      (node (ref "J2") (pin "GND") (pinfunction "1_GND") (pintype "passive"))
      (node (ref "J2") (pin "GND2") (pinfunction "4_GND2") (pintype "passive"))
      (node (ref "J3") (pin "GND") (pinfunction "1_GND") (pintype "passive"))
      (node (ref "J3") (pin "GND2") (pinfunction "4_GND2") (pintype "passive"))
      (node (ref "J4") (pin "GND") (pinfunction "1_GND") (pintype "passive"))
      (node (ref "J4") (pin "GND2") (pinfunction "4_GND2") (pintype "passive"))
      (node (ref "J5") (pin "GND") (pinfunction "1_GND") (pintype "passive"))
      (node (ref "J5") (pin "GND2") (pinfunction "4_GND2") (pintype "passive"))
      (node (ref "J6") (pin "GND") (pinfunction "1_GND") (pintype "passive"))
      (node (ref "J6") (pin "GND2") (pinfunction "4_GND2") (pintype "passive"))
      (node (ref "J7") (pin "GND") (pinfunction "1_GND") (pintype "passive"))
      (node (ref "J7") (pin "GND2") (pinfunction "4_GND2") (pintype "passive"))
      (node (ref "J8") (pin "GND") (pinfunction "1_GND") (pintype "passive"))
      (node (ref "J8") (pin "GND2") (pinfunction "4_GND2") (pintype "passive"))
      (node (ref "JP3") (pin "2") (pinfunction "2_2") (pintype "passive"))
      (node (ref "JP6") (pin "3") (pinfunction "3_3") (pintype "passive"))
      (node (ref "JP6") (pin "4") (pinfunction "4_4") (pintype "passive"))
      (node (ref "JP6") (pin "5") (pinfunction "5_5") (pintype "passive"))
      (node (ref "JP6") (pin "6") (pinfunction "6_6") (pintype "passive"))
      (node (ref "JP6") (pin "7") (pinfunction "7_7") (pintype "passive"))
      (node (ref "JP6") (pin "8") (pinfunction "8_8") (pintype "passive"))
      (node (ref "JP7") (pin "3") (pinfunction "3_3") (pintype "passive"))
      (node (ref "JP7") (pin "5") (pinfunction "5_5") (pintype "passive"))
      (node (ref "JP7") (pin "9") (pinfunction "9_9") (pintype "passive"))
      (node (ref "R14") (pin "P$3") (pinfunction "A_P$3") (pintype "passive"))
      (node (ref "R15") (pin "P$3") (pinfunction "A_P$3") (pintype "passive"))
      (node (ref "R2") (pin "P$3") (pinfunction "A_P$3") (pintype "passive"))
      (node (ref "R3") (pin "P$3") (pinfunction "A_P$3") (pintype "passive"))
      (node (ref "R31") (pin "1") (pinfunction "1_1") (pintype "passive"))
      (node (ref "R32") (pin "P$3") (pinfunction "A_P$3") (pintype "passive"))
      (node (ref "R33") (pin "P$3") (pinfunction "A_P$3") (pintype "passive"))
      (node (ref "R45") (pin "1") (pinfunction "1_1") (pintype "passive"))
      (node (ref "SW1") (pin "1") (pinfunction "1_1") (pintype "passive"))
      (node (ref "SW1") (pin "2") (pinfunction "2_2") (pintype "passive"))
      (node (ref "SW2") (pin "1") (pinfunction "1_1") (pintype "passive"))
      (node (ref "SW2") (pin "2") (pinfunction "2_2") (pintype "passive"))
      (node (ref "SW3") (pin "1") (pinfunction "1_1") (pintype "passive"))
      (node (ref "SW3") (pin "2") (pinfunction "2_2") (pintype "passive"))
      (node (ref "UC1") (pin "20") (pinfunction "PB2/BOOT1_20") (pintype "bidirectional"))
      (node (ref "UC1") (pin "23") (pinfunction "VSS_1_23") (pintype "power_in"))
      (node (ref "UC1") (pin "35") (pinfunction "VSS_2_35") (pintype "power_in"))
      (node (ref "UC1") (pin "44") (pinfunction "BOOT0_44") (pintype "input"))
      (node (ref "UC1") (pin "47") (pinfunction "VSS_3_47") (pintype "power_in"))
      (node (ref "UC1") (pin "8") (pinfunction "VSS_A_8") (pintype "power_in"))
    )
    (net (code "23") (name "JTCK") (class "Default")
      (node (ref "JP7") (pin "4") (pinfunction "4_4") (pintype "passive"))
      (node (ref "UC1") (pin "37") (pinfunction "PA14/JTCK/SWCLK_37") (pintype "bidirectional"))
    )
    (net (code "24") (name "JTDI") (class "Default")
      (node (ref "JP7") (pin "8") (pinfunction "8_8") (pintype "passive"))
      (node (ref "UC1") (pin "38") (pinfunction "PA15/JTDI_38") (pintype "bidirectional"))
    )
    (net (code "25") (name "JTDO") (class "Default")
      (node (ref "JP7") (pin "6") (pinfunction "6_6") (pintype "passive"))
      (node (ref "UC1") (pin "39") (pinfunction "PB3/JTDO_39") (pintype "bidirectional"))
    )
    (net (code "26") (name "JTMS") (class "Default")
      (node (ref "JP7") (pin "2") (pinfunction "2_2") (pintype "passive"))
      (node (ref "UC1") (pin "34") (pinfunction "PA13/JTMS/SWDIO_34") (pintype "bidirectional"))
    )
    (net (code "27") (name "Net-(C20-Pad1)") (class "Default")
      (node (ref "C20") (pin "1") (pinfunction "1_1") (pintype "passive"))
      (node (ref "R16") (pin "2") (pinfunction "2_2") (pintype "passive"))
      (node (ref "R20") (pin "1") (pinfunction "1_1") (pintype "passive"))
    )
    (net (code "28") (name "Net-(C21-Pad1)") (class "Default")
      (node (ref "C21") (pin "1") (pinfunction "1_1") (pintype "passive"))
      (node (ref "R17") (pin "2") (pinfunction "2_2") (pintype "passive"))
      (node (ref "R21") (pin "1") (pinfunction "1_1") (pintype "passive"))
    )
    (net (code "29") (name "Net-(C36-Pad1)") (class "Default")
      (node (ref "C36") (pin "1") (pinfunction "1_1") (pintype "passive"))
      (node (ref "R41") (pin "1") (pinfunction "1_1") (pintype "passive"))
    )
    (net (code "30") (name "Net-(C37-Pad1)") (class "Default")
      (node (ref "C37") (pin "1") (pinfunction "1_1") (pintype "passive"))
      (node (ref "R40") (pin "1") (pinfunction "1_1") (pintype "passive"))
    )
    (net (code "31") (name "Net-(C38-Pad1)") (class "Default")
      (node (ref "C38") (pin "1") (pinfunction "1_1") (pintype "passive"))
      (node (ref "R38") (pin "1") (pinfunction "1_1") (pintype "passive"))
    )
    (net (code "32") (name "Net-(C42-Pad1)") (class "Default")
      (node (ref "C42") (pin "1") (pinfunction "1_1") (pintype "passive"))
      (node (ref "R43") (pin "1") (pinfunction "1_1") (pintype "passive"))
    )
    (net (code "33") (name "Net-(C50-Pad1)") (class "Default")
      (node (ref "C50") (pin "1") (pinfunction "1_1") (pintype "passive"))
      (node (ref "R47") (pin "1") (pinfunction "1_1") (pintype "passive"))
    )
    (net (code "34") (name "Net-(C51-Pad1)") (class "Default")
      (node (ref "C51") (pin "1") (pinfunction "1_1") (pintype "passive"))
      (node (ref "R48") (pin "1") (pinfunction "1_1") (pintype "passive"))
    )
    (net (code "35") (name "Net-(C54-Pad1)") (class "Default")
      (node (ref "C54") (pin "1") (pinfunction "1_1") (pintype "passive"))
      (node (ref "R50") (pin "1") (pinfunction "1_1") (pintype "passive"))
    )
    (net (code "36") (name "Net-(C55-Pad1)") (class "Default")
      (node (ref "C55") (pin "1") (pinfunction "1_1") (pintype "passive"))
      (node (ref "R55") (pin "1") (pinfunction "1_1") (pintype "passive"))
    )
    (net (code "37") (name "Net-(D3-PadA)") (class "Default")
      (node (ref "D3") (pin "A") (pinfunction "A_A") (pintype "passive"))
      (node (ref "JP6") (pin "1") (pinfunction "1_1") (pintype "passive"))
      (node (ref "JP6") (pin "2") (pinfunction "2_2") (pintype "passive"))
    )
    (net (code "38") (name "Net-(IC1-OUTA)") (class "Default")
      (node (ref "IC1") (pin "4") (pinfunction "OUTA_4") (pintype "output"))
      (node (ref "R17") (pin "1") (pinfunction "1_1") (pintype "passive"))
    )
    (net (code "39") (name "Net-(IC1-OUTB)") (class "Default")
      (node (ref "IC1") (pin "3") (pinfunction "OUTB_3") (pintype "input"))
      (node (ref "R16") (pin "1") (pinfunction "1_1") (pintype "passive"))
    )
    (net (code "40") (name "Net-(IC2-VIN)") (class "Default")
      (node (ref "C16") (pin "+") (pinfunction "+_+") (pintype "passive"))
      (node (ref "IC2") (pin "3") (pinfunction "VIN_3") (pintype "input"))
      (node (ref "R11") (pin "2") (pinfunction "2_2") (pintype "passive"))
    )
    (net (code "41") (name "Net-(IC4A--IN)") (class "Default")
      (node (ref "C26") (pin "1") (pinfunction "1_1") (pintype "passive"))
      (node (ref "IC4") (pin "2") (pinfunction "-IN_2") (pintype "input"))
      (node (ref "R22") (pin "1") (pinfunction "1_1") (pintype "passive"))
      (node (ref "R25") (pin "2") (pinfunction "2_2") (pintype "passive"))
      (node (ref "R26") (pin "2") (pinfunction "2_2") (pintype "passive"))
    )
    (net (code "42") (name "Net-(IC4B--IN)") (class "Default")
      (node (ref "C27") (pin "1") (pinfunction "1_1") (pintype "passive"))
      (node (ref "IC4") (pin "6") (pinfunction "-IN_6") (pintype "input"))
      (node (ref "R23") (pin "1") (pinfunction "1_1") (pintype "passive"))
      (node (ref "R24") (pin "2") (pinfunction "2_2") (pintype "passive"))
      (node (ref "R28") (pin "2") (pinfunction "2_2") (pintype "passive"))
    )
    (net (code "43") (name "Net-(IC4C--IN)") (class "Default")
      (node (ref "C19") (pin "1") (pinfunction "1_1") (pintype "passive"))
      (node (ref "IC4") (pin "9") (pinfunction "-IN_9") (pintype "input"))
      (node (ref "R10") (pin "2") (pinfunction "2_2") (pintype "passive"))
      (node (ref "R13") (pin "2") (pinfunction "2_2") (pintype "passive"))
      (node (ref "R19") (pin "1") (pinfunction "1_1") (pintype "passive"))
    )
    (net (code "44") (name "Net-(IC4D--IN)") (class "Default")
      (node (ref "C18") (pin "1") (pinfunction "1_1") (pintype "passive"))
      (node (ref "IC4") (pin "13") (pinfunction "-IN_13") (pintype "input"))
      (node (ref "R12") (pin "2") (pinfunction "2_2") (pintype "passive"))
      (node (ref "R18") (pin "1") (pinfunction "1_1") (pintype "passive"))
      (node (ref "R9") (pin "2") (pinfunction "2_2") (pintype "passive"))
    )
    (net (code "45") (name "Net-(IC5A--IN)") (class "Default")
      (node (ref "IC5") (pin "1") (pinfunction "OUT_1") (pintype "output"))
      (node (ref "IC5") (pin "2") (pinfunction "-IN_2") (pintype "input"))
    )
    (net (code "46") (name "Net-(IC5B--IN)") (class "Default")
      (node (ref "C30") (pin "1") (pinfunction "1_1") (pintype "passive"))
      (node (ref "IC5") (pin "6") (pinfunction "-IN_6") (pintype "input"))
      (node (ref "IC8") (pin "12") (pinfunction "OUT_12") (pintype "output"))
      (node (ref "R30") (pin "2") (pinfunction "2_2") (pintype "passive"))
      (node (ref "R32") (pin "P$1") (pinfunction "E_P$1") (pintype "passive"))
      (node (ref "R65") (pin "2") (pinfunction "2_2") (pintype "passive"))
    )
    (net (code "47") (name "Net-(IC6A--IN)") (class "Default")
      (node (ref "IC6") (pin "1") (pinfunction "OUT_1") (pintype "output"))
      (node (ref "IC6") (pin "2") (pinfunction "-IN_2") (pintype "input"))
    )
    (net (code "48") (name "Net-(IC6B--IN)") (class "Default")
      (node (ref "C31") (pin "1") (pinfunction "1_1") (pintype "passive"))
      (node (ref "IC6") (pin "6") (pinfunction "-IN_6") (pintype "input"))
      (node (ref "IC9") (pin "13") (pinfunction "OUT_13") (pintype "output"))
      (node (ref "R29") (pin "2") (pinfunction "2_2") (pintype "passive"))
      (node (ref "R33") (pin "P$1") (pinfunction "E_P$1") (pintype "passive"))
      (node (ref "R64") (pin "2") (pinfunction "2_2") (pintype "passive"))
    )
    (net (code "49") (name "Net-(IC7A--IN)") (class "Default")
      (node (ref "C53") (pin "1") (pinfunction "1_1") (pintype "passive"))
      (node (ref "IC7") (pin "2") (pinfunction "-IN_2") (pintype "input"))
      (node (ref "IC8") (pin "4") (pinfunction "OUT_4") (pintype "output"))
    )
    (net (code "50") (name "Net-(IC7A-OUT)") (class "Default")
      (node (ref "C53") (pin "2") (pinfunction "2_2") (pintype "passive"))
      (node (ref "IC7") (pin "1") (pinfunction "OUT_1") (pintype "output"))
      (node (ref "R49") (pin "2") (pinfunction "2_2") (pintype "passive"))
      (node (ref "R51") (pin "1") (pinfunction "1_1") (pintype "passive"))
    )
    (net (code "51") (name "Net-(IC7B--IN)") (class "Default")
      (node (ref "C40") (pin "1") (pinfunction "1_1") (pintype "passive"))
      (node (ref "IC7") (pin "6") (pinfunction "-IN_6") (pintype "input"))
      (node (ref "IC8") (pin "5") (pinfunction "OUT_5") (pintype "output"))
    )
    (net (code "52") (name "Net-(IC7B-OUT)") (class "Default")
      (node (ref "C40") (pin "2") (pinfunction "2_2") (pintype "passive"))
      (node (ref "IC7") (pin "7") (pinfunction "OUT_7") (pintype "output"))
      (node (ref "R52") (pin "2") (pinfunction "2_2") (pintype "passive"))
      (node (ref "R61") (pin "1") (pinfunction "1_1") (pintype "passive"))
    )
    (net (code "53") (name "Net-(IC8A-IN)") (class "Default")
      (node (ref "IC8") (pin "13") (pinfunction "OUT_13") (pintype "output"))
      (node (ref "IC8") (pin "2") (pinfunction "IN_2") (pintype "input"))
      (node (ref "R49") (pin "1") (pinfunction "1_1") (pintype "passive"))
      (node (ref "R50") (pin "2") (pinfunction "2_2") (pintype "passive"))
    )
    (net (code "54") (name "Net-(IC8B-IN)") (class "Default")
      (node (ref "IC8") (pin "7") (pinfunction "IN_7") (pintype "input"))
      (node (ref "R47") (pin "2") (pinfunction "2_2") (pintype "passive"))
      (node (ref "R51") (pin "2") (pinfunction "2_2") (pintype "passive"))
      (node (ref "R52") (pin "1") (pinfunction "1_1") (pintype "passive"))
    )
    (net (code "55") (name "Net-(IC8C-CTRL)") (class "Default")
      (node (ref "IC8") (pin "11") (pinfunction "CTRL_11") (pintype "input"))
      (node (ref "R27") (pin "P$2") (pinfunction "S_P$2") (pintype "passive"))
    )
    (net (code "56") (name "Net-(IC8C-IN)") (class "Default")
      (node (ref "IC8") (pin "10") (pinfunction "IN_10") (pintype "input"))
      (node (ref "R37") (pin "2") (pinfunction "2_2") (pintype "passive"))
      (node (ref "R38") (pin "2") (pinfunction "2_2") (pintype "passive"))
    )
    (net (code "57") (name "Net-(IC8D-IN)") (class "Default")
      (node (ref "IC8") (pin "15") (pinfunction "IN_15") (pintype "input"))
      (node (ref "R41") (pin "2") (pinfunction "2_2") (pintype "passive"))
      (node (ref "R42") (pin "2") (pinfunction "2_2") (pintype "passive"))
    )
    (net (code "58") (name "Net-(IC9A-IN)") (class "Default")
      (node (ref "IC9") (pin "2") (pinfunction "IN_2") (pintype "input"))
      (node (ref "R48") (pin "2") (pinfunction "2_2") (pintype "passive"))
      (node (ref "R53") (pin "1") (pinfunction "1_1") (pintype "passive"))
      (node (ref "R54") (pin "2") (pinfunction "2_2") (pintype "passive"))
    )
    (net (code "59") (name "Net-(IC9B-IN)") (class "Default")
      (node (ref "IC9") (pin "12") (pinfunction "OUT_12") (pintype "output"))
      (node (ref "IC9") (pin "7") (pinfunction "IN_7") (pintype "input"))
      (node (ref "R55") (pin "2") (pinfunction "2_2") (pintype "passive"))
      (node (ref "R56") (pin "1") (pinfunction "1_1") (pintype "passive"))
    )
    (net (code "60") (name "Net-(IC9C-IN)") (class "Default")
      (node (ref "IC9") (pin "10") (pinfunction "IN_10") (pintype "input"))
      (node (ref "R39") (pin "2") (pinfunction "2_2") (pintype "passive"))
      (node (ref "R40") (pin "2") (pinfunction "2_2") (pintype "passive"))
    )
    (net (code "61") (name "Net-(IC9D-CTRL)") (class "Default")
      (node (ref "IC9") (pin "14") (pinfunction "CTRL_14") (pintype "input"))
      (node (ref "R36") (pin "P$2") (pinfunction "S_P$2") (pintype "passive"))
    )
    (net (code "62") (name "Net-(IC9D-IN)") (class "Default")
      (node (ref "IC9") (pin "15") (pinfunction "IN_15") (pintype "input"))
      (node (ref "R43") (pin "2") (pinfunction "2_2") (pintype "passive"))
      (node (ref "R44") (pin "2") (pinfunction "2_2") (pintype "passive"))
    )
    (net (code "63") (name "Net-(IC10A--IN)") (class "Default")
      (node (ref "C52") (pin "1") (pinfunction "1_1") (pintype "passive"))
      (node (ref "IC10") (pin "2") (pinfunction "-IN_2") (pintype "input"))
      (node (ref "IC9") (pin "5") (pinfunction "OUT_5") (pintype "output"))
    )
    (net (code "64") (name "Net-(IC10A-OUT)") (class "Default")
      (node (ref "C52") (pin "2") (pinfunction "2_2") (pintype "passive"))
      (node (ref "IC10") (pin "1") (pinfunction "OUT_1") (pintype "output"))
      (node (ref "R54") (pin "1") (pinfunction "1_1") (pintype "passive"))
      (node (ref "R56") (pin "2") (pinfunction "2_2") (pintype "passive"))
    )
    (net (code "65") (name "Net-(IC10B--IN)") (class "Default")
      (node (ref "C43") (pin "1") (pinfunction "1_1") (pintype "passive"))
      (node (ref "IC10") (pin "6") (pinfunction "-IN_6") (pintype "input"))
      (node (ref "IC9") (pin "4") (pinfunction "OUT_4") (pintype "output"))
    )
    (net (code "66") (name "Net-(IC10B-OUT)") (class "Default")
      (node (ref "C43") (pin "2") (pinfunction "2_2") (pintype "passive"))
      (node (ref "IC10") (pin "7") (pinfunction "OUT_7") (pintype "output"))
      (node (ref "R53") (pin "2") (pinfunction "2_2") (pintype "passive"))
      (node (ref "R62") (pin "1") (pinfunction "1_1") (pintype "passive"))
    )
    (net (code "67") (name "Net-(J1-2)") (class "Default")
      (node (ref "J1") (pin "TIP") (pinfunction "2_TIP") (pintype "passive"))
      (node (ref "R25") (pin "1") (pinfunction "1_1") (pintype "passive"))
    )
    (net (code "68") (name "Net-(J2-2)") (class "Default")
      (node (ref "J2") (pin "TIP") (pinfunction "2_TIP") (pintype "passive"))
      (node (ref "R12") (pin "1") (pinfunction "1_1") (pintype "passive"))
      (node (ref "R42") (pin "1") (pinfunction "1_1") (pintype "passive"))
    )
    (net (code "69") (name "Net-(J2-3)") (class "Default")
      (node (ref "J2") (pin "SW") (pinfunction "3_SW") (pintype "passive"))
      (node (ref "R59") (pin "1") (pinfunction "1_1") (pintype "passive"))
    )
    (net (code "70") (name "Net-(J3-2)") (class "Default")
      (node (ref "J3") (pin "TIP") (pinfunction "2_TIP") (pintype "passive"))
      (node (ref "R13") (pin "1") (pinfunction "1_1") (pintype "passive"))
      (node (ref "R39") (pin "1") (pinfunction "1_1") (pintype "passive"))
    )
    (net (code "71") (name "Net-(J3-3)") (class "Default")
      (node (ref "J3") (pin "SW") (pinfunction "3_SW") (pintype "passive"))
      (node (ref "R58") (pin "1") (pinfunction "1_1") (pintype "passive"))
    )
    (net (code "72") (name "Net-(J4-2)") (class "Default")
      (node (ref "J4") (pin "TIP") (pinfunction "2_TIP") (pintype "passive"))
      (node (ref "R28") (pin "1") (pinfunction "1_1") (pintype "passive"))
    )
    (net (code "73") (name "Net-(J5-2)") (class "Default")
      (node (ref "J5") (pin "TIP") (pinfunction "2_TIP") (pintype "passive"))
      (node (ref "R34") (pin "1") (pinfunction "1_1") (pintype "passive"))
    )
    (net (code "74") (name "Net-(J5-3)") (class "Default")
      (node (ref "J5") (pin "SW") (pinfunction "3_SW") (pintype "passive"))
      (node (ref "R60") (pin "1") (pinfunction "1_1") (pintype "passive"))
    )
    (net (code "75") (name "Net-(J6-2)") (class "Default")
      (node (ref "J6") (pin "TIP") (pinfunction "2_TIP") (pintype "passive"))
      (node (ref "R61") (pin "2") (pinfunction "2_2") (pintype "passive"))
    )
    (net (code "76") (name "Net-(J7-2)") (class "Default")
      (node (ref "J7") (pin "TIP") (pinfunction "2_TIP") (pintype "passive"))
      (node (ref "R62") (pin "2") (pinfunction "2_2") (pintype "passive"))
    )
    (net (code "77") (name "Net-(J8-2)") (class "Default")
      (node (ref "J8") (pin "TIP") (pinfunction "2_TIP") (pintype "passive"))
      (node (ref "R35") (pin "1") (pinfunction "1_1") (pintype "passive"))
    )
    (net (code "78") (name "Net-(J8-3)") (class "Default")
      (node (ref "J8") (pin "SW") (pinfunction "3_SW") (pintype "passive"))
      (node (ref "R63") (pin "1") (pinfunction "1_1") (pintype "passive"))
    )
    (net (code "79") (name "Net-(JP6-Pad10)") (class "Default")
      (node (ref "JP6") (pin "10") (pinfunction "10_10") (pintype "passive"))
      (node (ref "JP6") (pin "9") (pinfunction "9_9") (pintype "passive"))
      (node (ref "P1") (pin "2") (pinfunction "2_2") (pintype "bidirectional"))
    )
    (net (code "80") (name "Net-(R27-A)") (class "Default")
      (node (ref "R27") (pin "P$3") (pinfunction "A_P$3") (pintype "passive"))
      (node (ref "R31") (pin "2") (pinfunction "2_2") (pintype "passive"))
    )
    (net (code "81") (name "Net-(R32-S)") (class "Default")
      (node (ref "R32") (pin "P$2") (pinfunction "S_P$2") (pintype "passive"))
      (node (ref "R34") (pin "2") (pinfunction "2_2") (pintype "passive"))
    )
    (net (code "82") (name "Net-(R33-S)") (class "Default")
      (node (ref "R33") (pin "P$2") (pinfunction "S_P$2") (pintype "passive"))
      (node (ref "R35") (pin "2") (pinfunction "2_2") (pintype "passive"))
    )
    (net (code "83") (name "Net-(R36-A)") (class "Default")
      (node (ref "R36") (pin "P$3") (pinfunction "A_P$3") (pintype "passive"))
      (node (ref "R45") (pin "2") (pinfunction "2_2") (pintype "passive"))
    )
    (net (code "84") (name "Net-(UC1-PA10{slash}USART1_RX{slash}TIM1_CH3)") (class "Default")
      (node (ref "R4") (pin "1") (pinfunction "1_1") (pintype "passive"))
      (node (ref "UC1") (pin "31") (pinfunction "PA10/USART1_RX/TIM1_CH3_31") (pintype "bidirectional"))
    )
    (net (code "85") (name "Net-(UC1-PA11{slash}USART1_CTS{slash}CAN_RX{slash}TIM1_CH4{slash}USBDM)") (class "Default")
      (node (ref "R5") (pin "1") (pinfunction "1_1") (pintype "passive"))
      (node (ref "UC1") (pin "32") (pinfunction "PA11/USART1_CTS/CAN_RX/TIM1_CH4/USBDM_32") (pintype "bidirectional"))
    )
    (net (code "86") (name "Net-(UC1-PD0-OSC_IN)") (class "Default")
      (node (ref "C5") (pin "2") (pinfunction "2_2") (pintype "passive"))
      (node (ref "Q1") (pin "2") (pinfunction "2_2") (pintype "passive"))
      (node (ref "UC1") (pin "5") (pinfunction "PD0-OSC_IN_5") (pintype "input"))
    )
    (net (code "87") (name "Net-(UC1-PD1-OSC_OUT)") (class "Default")
      (node (ref "C12") (pin "2") (pinfunction "2_2") (pintype "passive"))
      (node (ref "Q1") (pin "1") (pinfunction "1_1") (pintype "passive"))
      (node (ref "UC1") (pin "6") (pinfunction "PD1-OSC_OUT_6") (pintype "input"))
    )
    (net (code "88") (name "PWM_CUTOFF_1") (class "Default")
      (node (ref "C6") (pin "1") (pinfunction "1_1") (pintype "passive"))
      (node (ref "IC8") (pin "3") (pinfunction "CTRL_3") (pintype "input"))
      (node (ref "IC8") (pin "6") (pinfunction "CTRL_6") (pintype "input"))
      (node (ref "R4") (pin "2") (pinfunction "2_2") (pintype "passive"))
    )
    (net (code "89") (name "PWM_CUTOFF_2") (class "Default")
      (node (ref "C7") (pin "1") (pinfunction "1_1") (pintype "passive"))
      (node (ref "IC9") (pin "3") (pinfunction "CTRL_3") (pintype "input"))
      (node (ref "IC9") (pin "6") (pinfunction "CTRL_6") (pintype "input"))
      (node (ref "R5") (pin "2") (pinfunction "2_2") (pintype "passive"))
    )
    (net (code "90") (name "RESET") (class "Default")
      (node (ref "JP7") (pin "10") (pinfunction "10_10") (pintype "passive"))
      (node (ref "R1") (pin "1") (pinfunction "1_1") (pintype "passive"))
      (node (ref "UC1") (pin "7") (pinfunction "NRST_7") (pintype "input"))
    )
    (net (code "91") (name "SHAPE_1") (class "Default")
      (node (ref "R2") (pin "P$2") (pinfunction "S_P$2") (pintype "passive"))
      (node (ref "UC1") (pin "12") (pinfunction "PA2/USART2_TX/ADC12_IN2/TIM2_CH3_12") (pintype "bidirectional"))
    )
    (net (code "92") (name "SHAPE_2") (class "Default")
      (node (ref "R3") (pin "P$2") (pinfunction "S_P$2") (pintype "passive"))
      (node (ref "UC1") (pin "11") (pinfunction "PA1/USART2_RTS/ADC12_IN1/TIM2_CH2_11") (pintype "bidirectional"))
    )
    (net (code "93") (name "SW_METER") (class "Default")
      (node (ref "SW3") (pin "3") (pinfunction "3_3") (pintype "passive"))
      (node (ref "SW3") (pin "4") (pinfunction "4_4") (pintype "passive"))
      (node (ref "UC1") (pin "42") (pinfunction "PB6/I2C1_SCL/TIM4_CH1_42") (pintype "input"))
    )
    (net (code "94") (name "SW_MODE_1") (class "Default")
      (node (ref "SW1") (pin "3") (pinfunction "3_3") (pintype "passive"))
      (node (ref "SW1") (pin "4") (pinfunction "4_4") (pintype "passive"))
      (node (ref "UC1") (pin "41") (pinfunction "PB5/I2C1_SMBA_41") (pintype "input"))
    )
    (net (code "95") (name "SW_MODE_2") (class "Default")
      (node (ref "SW2") (pin "3") (pinfunction "3_3") (pintype "passive"))
      (node (ref "SW2") (pin "4") (pinfunction "4_4") (pintype "passive"))
      (node (ref "UC1") (pin "40") (pinfunction "PB4/NJTRST_40") (pintype "bidirectional"))
    )
    (net (code "96") (name "VCA_CONTROL_1") (class "Default")
      (node (ref "C30") (pin "2") (pinfunction "2_2") (pintype "passive"))
      (node (ref "D5") (pin "C") (pinfunction "C_C") (pintype "passive"))
      (node (ref "IC5") (pin "7") (pinfunction "OUT_7") (pintype "output"))
      (node (ref "IC8") (pin "14") (pinfunction "CTRL_14") (pintype "input"))
      (node (ref "R27") (pin "P$1") (pinfunction "E_P$1") (pintype "passive"))
      (node (ref "R6") (pin "2") (pinfunction "2_2") (pintype "passive"))
      (node (ref "TP1") (pin "P$1") (pinfunction "1_P$1") (pintype "bidirectional"))
    )
    (net (code "97") (name "VCA_CONTROL_2") (class "Default")
      (node (ref "C31") (pin "2") (pinfunction "2_2") (pintype "passive"))
      (node (ref "D4") (pin "C") (pinfunction "C_C") (pintype "passive"))
      (node (ref "IC6") (pin "7") (pinfunction "OUT_7") (pintype "output"))
      (node (ref "IC9") (pin "11") (pinfunction "CTRL_11") (pintype "input"))
      (node (ref "R36") (pin "P$1") (pinfunction "E_P$1") (pintype "passive"))
      (node (ref "R7") (pin "2") (pinfunction "2_2") (pintype "passive"))
      (node (ref "TP2") (pin "P$1") (pinfunction "1_P$1") (pintype "bidirectional"))
    )
    (net (code "98") (name "VCC") (class "Default")
      (node (ref "C24") (pin "+") (pinfunction "+_+") (pintype "passive"))
      (node (ref "C29") (pin "1") (pinfunction "1_1") (pintype "passive"))
      (node (ref "C32") (pin "1") (pinfunction "1_1") (pintype "passive"))
      (node (ref "C35") (pin "1") (pinfunction "1_1") (pintype "passive"))
      (node (ref "C41") (pin "1") (pinfunction "1_1") (pintype "passive"))
      (node (ref "C45") (pin "1") (pinfunction "1_1") (pintype "passive"))
      (node (ref "C46") (pin "1") (pinfunction "1_1") (pintype "passive"))
      (node (ref "D3") (pin "C") (pinfunction "C_C") (pintype "passive"))
      (node (ref "IC10") (pin "8") (pinfunction "V+_8") (pintype "power_in"))
      (node (ref "IC5") (pin "8") (pinfunction "V+_8") (pintype "power_in"))
      (node (ref "IC6") (pin "8") (pinfunction "V+_8") (pintype "power_in"))
      (node (ref "IC7") (pin "8") (pinfunction "V+_8") (pintype "power_in"))
      (node (ref "IC8") (pin "16") (pinfunction "V+_16") (pintype "power_in"))
      (node (ref "IC9") (pin "16") (pinfunction "V+_16") (pintype "power_in"))
      (node (ref "R11") (pin "1") (pinfunction "1_1") (pintype "passive"))
      (node (ref "R57") (pin "1") (pinfunction "1_1") (pintype "passive"))
    )
    (net (code "99") (name "VEE") (class "Default")
      (node (ref "C28") (pin "-") (pinfunction "-_-") (pintype "passive"))
      (node (ref "C33") (pin "2") (pinfunction "2_2") (pintype "passive"))
      (node (ref "C34") (pin "2") (pinfunction "2_2") (pintype "passive"))
      (node (ref "C39") (pin "2") (pinfunction "2_2") (pintype "passive"))
      (node (ref "C44") (pin "2") (pinfunction "2_2") (pintype "passive"))
      (node (ref "C48") (pin "2") (pinfunction "2_2") (pintype "passive"))
      (node (ref "C49") (pin "2") (pinfunction "2_2") (pintype "passive"))
      (node (ref "D6") (pin "A") (pinfunction "A_A") (pintype "passive"))
      (node (ref "IC10") (pin "4") (pinfunction "V-_4") (pintype "power_in"))
      (node (ref "IC5") (pin "4") (pinfunction "V-_4") (pintype "power_in"))
      (node (ref "IC6") (pin "4") (pinfunction "V-_4") (pintype "power_in"))
      (node (ref "IC7") (pin "4") (pinfunction "V-_4") (pintype "power_in"))
      (node (ref "IC8") (pin "9") (pinfunction "V-_9") (pintype "power_in"))
      (node (ref "IC9") (pin "9") (pinfunction "V-_9") (pintype "power_in"))
      (node (ref "P1") (pin "1") (pinfunction "1_1") (pintype "bidirectional"))
      (node (ref "R46") (pin "1") (pinfunction "1_1") (pintype "passive"))
    )
    (net (code "100") (name "unconnected-(IC8E-MODE-Pad1)") (class "Default")
      (node (ref "IC8") (pin "1") (pinfunction "MODE_1") (pintype "input"))
    )
    (net (code "101") (name "unconnected-(IC9E-MODE-Pad1)") (class "Default")
      (node (ref "IC9") (pin "1") (pinfunction "MODE_1") (pintype "input"))
    )
    (net (code "102") (name "unconnected-(J1-3-PadSW)") (class "Default")
      (node (ref "J1") (pin "SW") (pinfunction "3_SW") (pintype "passive"))
    )
    (net (code "103") (name "unconnected-(J4-3-PadSW)") (class "Default")
      (node (ref "J4") (pin "SW") (pinfunction "3_SW") (pintype "passive"))
    )
    (net (code "104") (name "unconnected-(J6-3-PadSW)") (class "Default")
      (node (ref "J6") (pin "SW") (pinfunction "3_SW") (pintype "passive"))
    )
    (net (code "105") (name "unconnected-(J7-3-PadSW)") (class "Default")
      (node (ref "J7") (pin "SW") (pinfunction "3_SW") (pintype "passive"))
    )
    (net (code "106") (name "unconnected-(JP7-Pad7)") (class "Default")
      (node (ref "JP7") (pin "7") (pinfunction "7_7") (pintype "passive"))
    )
    (net (code "107") (name "unconnected-(UC1-PA8{slash}USART1_CK{slash}TIM1_CH1{slash}MCO-Pad29)") (class "Default")
      (node (ref "UC1") (pin "29") (pinfunction "PA8/USART1_CK/TIM1_CH1/MCO_29") (pintype "bidirectional"))
    )
    (net (code "108") (name "unconnected-(UC1-PA9{slash}USART1_TX{slash}TIM1_CH2-Pad30)") (class "Default")
      (node (ref "UC1") (pin "30") (pinfunction "PA9/USART1_TX/TIM1_CH2_30") (pintype "input"))
    )
    (net (code "109") (name "unconnected-(UC1-PA12{slash}USART1_RTS{slash}CAN_TX{slash}TIM1_ETR{slash}USBDP-Pad33)") (class "Default")
      (node (ref "UC1") (pin "33") (pinfunction "PA12/USART1_RTS/CAN_TX/TIM1_ETR/USBDP_33") (pintype "bidirectional"))
    )
    (net (code "110") (name "unconnected-(UC1-PB8{slash}TIM4_CH3-Pad45)") (class "Default")
      (node (ref "UC1") (pin "45") (pinfunction "PB8/TIM4_CH3_45") (pintype "bidirectional"))
    )
    (net (code "111") (name "unconnected-(UC1-PB9{slash}TIM4_CH4-Pad46)") (class "Default")
      (node (ref "UC1") (pin "46") (pinfunction "PB9/TIM4_CH4_46") (pintype "input"))
    )
    (net (code "112") (name "unconnected-(UC1-PB14{slash}SPI2_MISO{slash}USART3_RTS{slash}TIM1_CH2N-Pad27)") (class "Default")
      (node (ref "UC1") (pin "27") (pinfunction "PB14/SPI2_MISO/USART3_RTS/TIM1_CH2N_27") (pintype "input"))
    )
    (net (code "113") (name "unconnected-(UC1-PC13-TAMPER-RTC-Pad2)") (class "Default")
      (node (ref "UC1") (pin "2") (pinfunction "PC13-TAMPER-RTC_2") (pintype "input"))
    )
    (net (code "114") (name "unconnected-(UC1-PC14-OSC32_IN-Pad3)") (class "Default")
      (node (ref "UC1") (pin "3") (pinfunction "PC14-OSC32_IN_3") (pintype "input"))
    )
    (net (code "115") (name "unconnected-(UC1-PC15-OSC32_OUT-Pad4)") (class "Default")
      (node (ref "UC1") (pin "4") (pinfunction "PC15-OSC32_OUT_4") (pintype "input"))
    )
  )
)
